# SDRAM_DDR3_4x16.net
KiCad netlist of a schematic drawn in Altium Designer
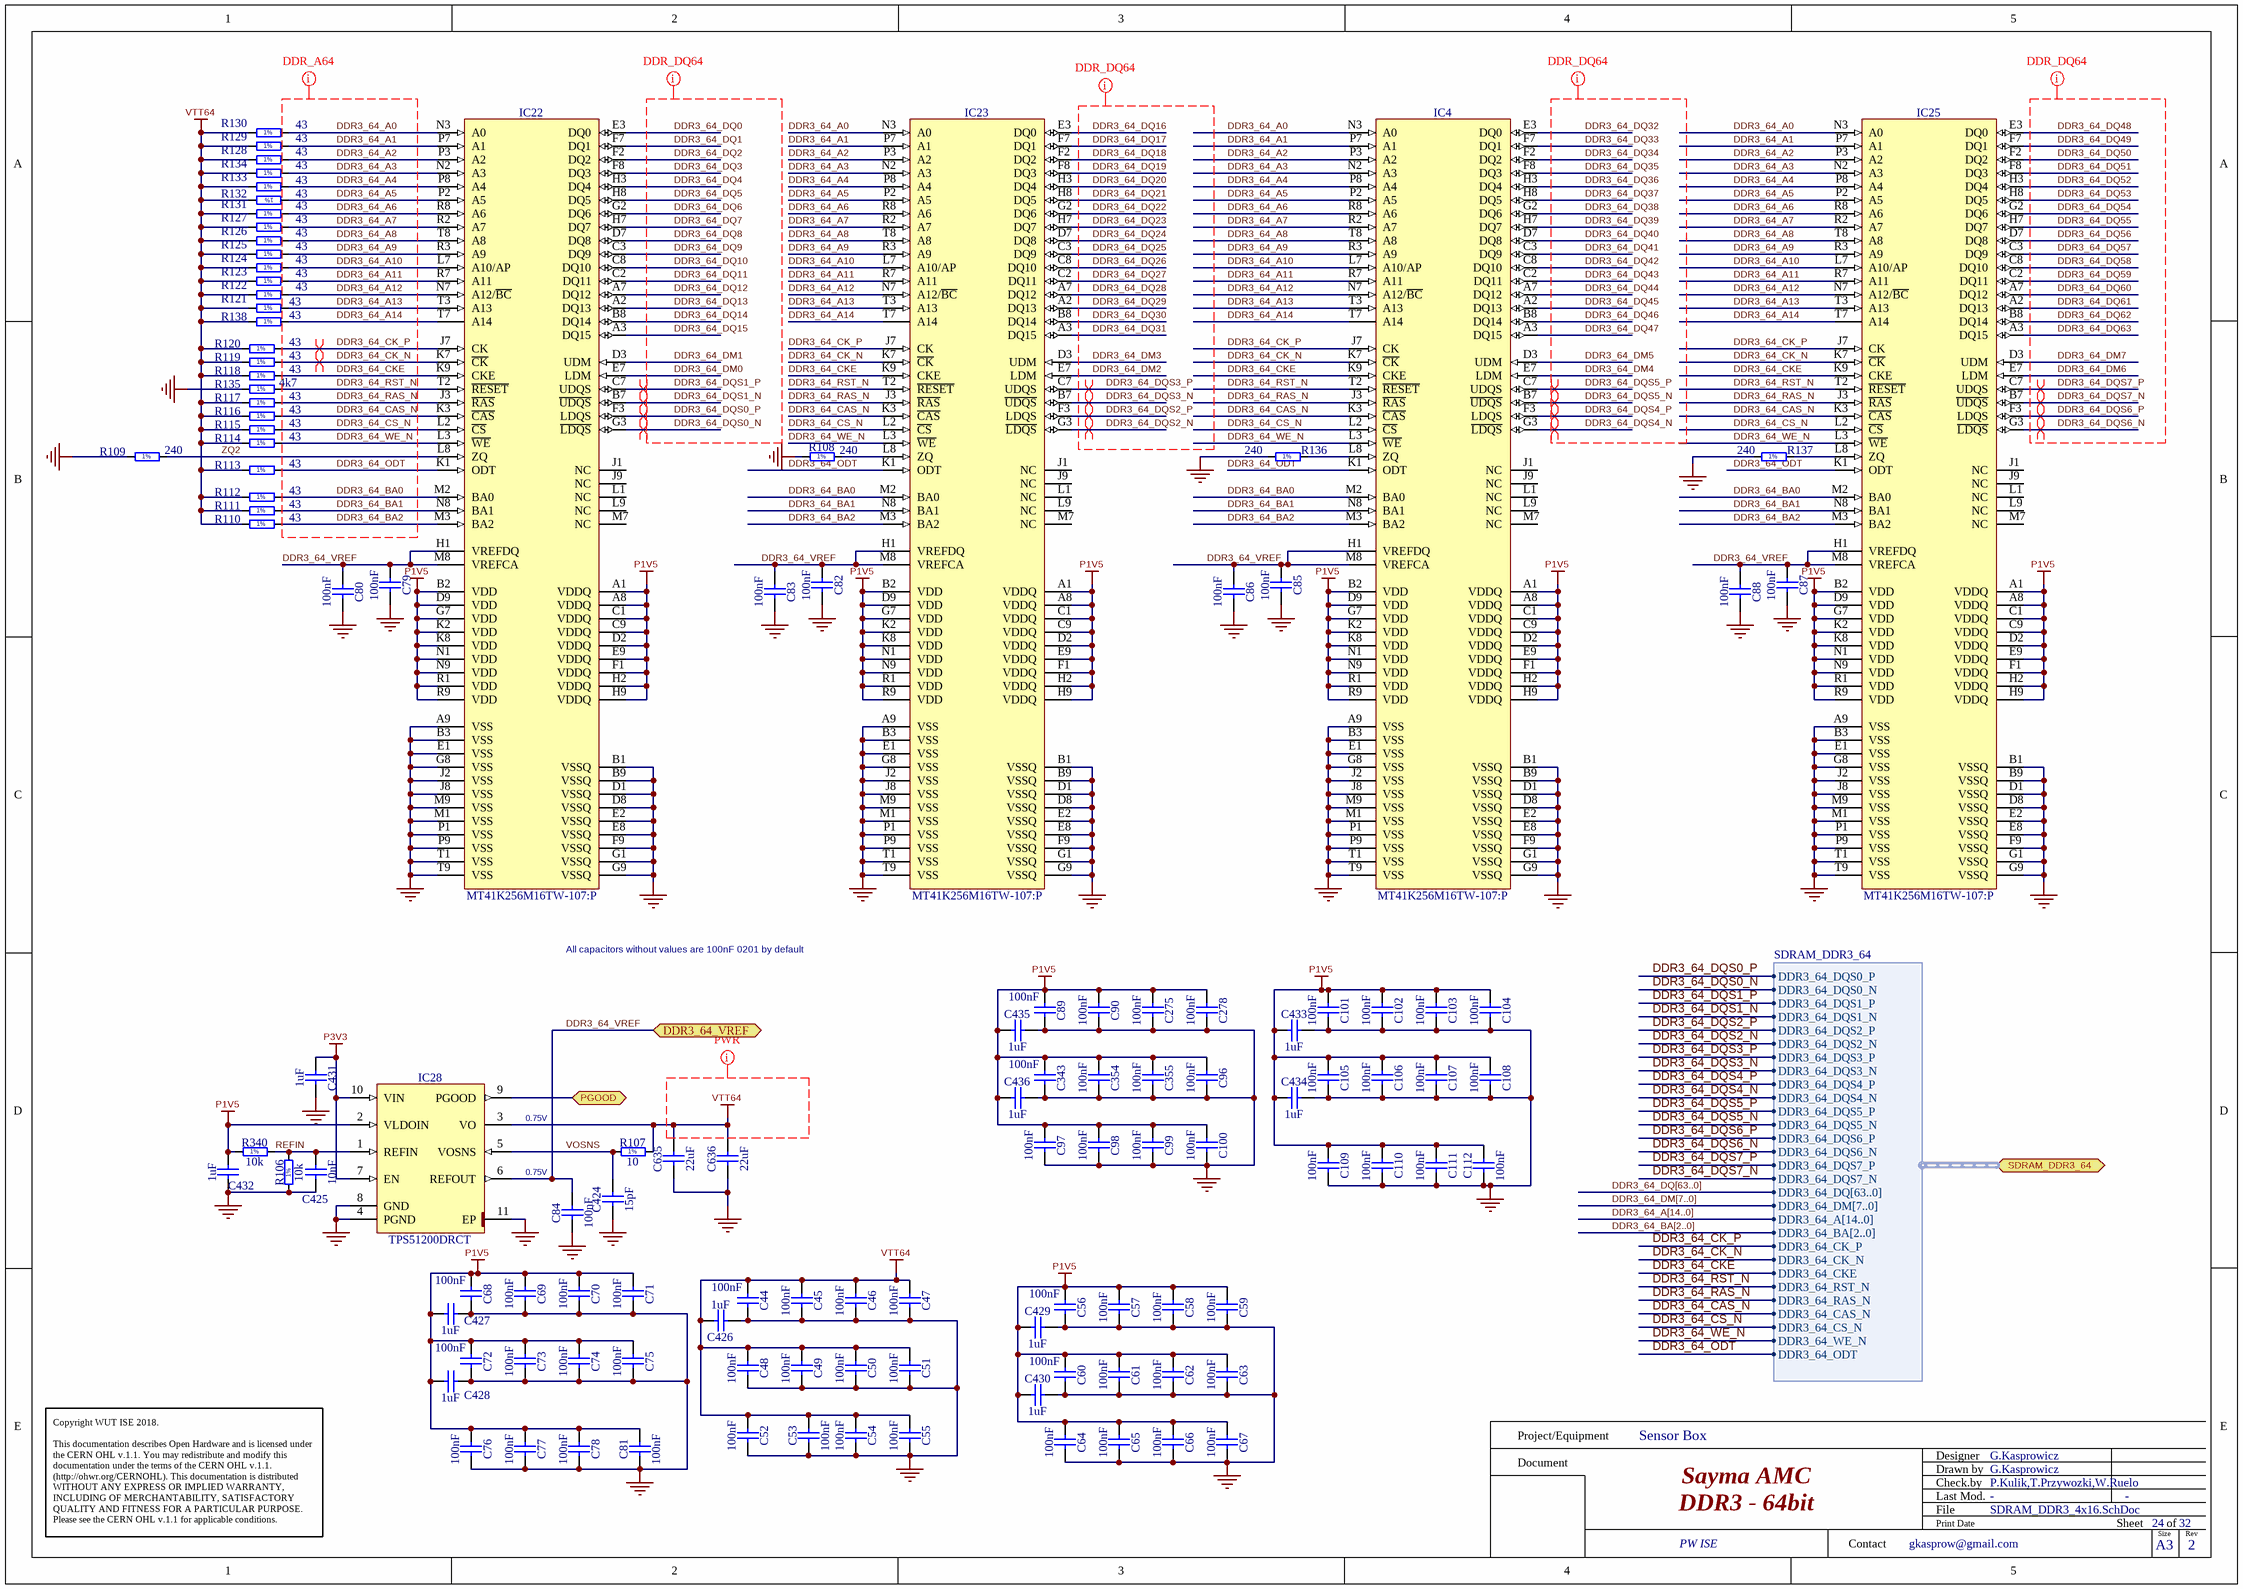
[diagram p0: SDRAM_DDR3_4x16.SchDoc]

(export (version "E")
  (design (tool "Eeschema 10.0.6"))
  (components
    (comp (ref "C44")
      (value "100nF")
      (footprint "CAPC0603X33N")
      (description "Non-polarised capacitor")
      (fields
        (field (name "MANUFACTURER PART NUMBER") "CC0201_100NF_6.3V_10%_X5R")
        (field (name "MANUFACTURER") "GENERIC")
        (field (name "AUTHOR") "CERN DEM JLC")
      )
      (libsource (lib "Capacitors") (part "Capacitor - non polarized"))
    )
    (comp (ref "C45")
      (value "100nF")
      (footprint "CAPC0603X33N")
      (description "Non-polarised capacitor")
      (fields
        (field (name "MANUFACTURER PART NUMBER") "CC0201_100NF_6.3V_10%_X5R")
        (field (name "MANUFACTURER") "GENERIC")
        (field (name "AUTHOR") "CERN DEM JLC")
      )
      (libsource (lib "Capacitors") (part "Capacitor - non polarized"))
    )
    (comp (ref "C46")
      (value "100nF")
      (footprint "CAPC0603X33N")
      (description "Non-polarised capacitor")
      (fields
        (field (name "MANUFACTURER PART NUMBER") "CC0201_100NF_6.3V_10%_X5R")
        (field (name "MANUFACTURER") "GENERIC")
        (field (name "AUTHOR") "CERN DEM JLC")
      )
      (libsource (lib "Capacitors") (part "Capacitor - non polarized"))
    )
    (comp (ref "C47")
      (value "100nF")
      (footprint "CAPC0603X33N")
      (description "Non-polarised capacitor")
      (fields
        (field (name "MANUFACTURER PART NUMBER") "CC0201_100NF_6.3V_10%_X5R")
        (field (name "MANUFACTURER") "GENERIC")
        (field (name "AUTHOR") "CERN DEM JLC")
      )
      (libsource (lib "Capacitors") (part "Capacitor - non polarized"))
    )
    (comp (ref "C48")
      (value "100nF")
      (footprint "CAPC0603X33N")
      (description "Non-polarised capacitor")
      (fields
        (field (name "MANUFACTURER PART NUMBER") "CC0201_100NF_6.3V_10%_X5R")
        (field (name "MANUFACTURER") "GENERIC")
        (field (name "AUTHOR") "CERN DEM JLC")
      )
      (libsource (lib "Capacitors") (part "Capacitor - non polarized"))
    )
    (comp (ref "C49")
      (value "100nF")
      (footprint "CAPC0603X33N")
      (description "Non-polarised capacitor")
      (fields
        (field (name "MANUFACTURER PART NUMBER") "CC0201_100NF_6.3V_10%_X5R")
        (field (name "MANUFACTURER") "GENERIC")
        (field (name "AUTHOR") "CERN DEM JLC")
      )
      (libsource (lib "Capacitors") (part "Capacitor - non polarized"))
    )
    (comp (ref "C50")
      (value "100nF")
      (footprint "CAPC0603X33N")
      (description "Non-polarised capacitor")
      (fields
        (field (name "MANUFACTURER PART NUMBER") "CC0201_100NF_6.3V_10%_X5R")
        (field (name "MANUFACTURER") "GENERIC")
        (field (name "AUTHOR") "CERN DEM JLC")
      )
      (libsource (lib "Capacitors") (part "Capacitor - non polarized"))
    )
    (comp (ref "C51")
      (value "100nF")
      (footprint "CAPC0603X33N")
      (description "Non-polarised capacitor")
      (fields
        (field (name "MANUFACTURER PART NUMBER") "CC0201_100NF_6.3V_10%_X5R")
        (field (name "MANUFACTURER") "GENERIC")
        (field (name "AUTHOR") "CERN DEM JLC")
      )
      (libsource (lib "Capacitors") (part "Capacitor - non polarized"))
    )
    (comp (ref "C52")
      (value "100nF")
      (footprint "CAPC0603X33N")
      (description "Non-polarised capacitor")
      (fields
        (field (name "MANUFACTURER PART NUMBER") "CC0201_100NF_6.3V_10%_X5R")
        (field (name "MANUFACTURER") "GENERIC")
        (field (name "AUTHOR") "CERN DEM JLC")
      )
      (libsource (lib "Capacitors") (part "Capacitor - non polarized"))
    )
    (comp (ref "C53")
      (value "100nF")
      (footprint "CAPC0603X33N")
      (description "Non-polarised capacitor")
      (fields
        (field (name "MANUFACTURER PART NUMBER") "CC0201_100NF_6.3V_10%_X5R")
        (field (name "MANUFACTURER") "GENERIC")
        (field (name "AUTHOR") "CERN DEM JLC")
      )
      (libsource (lib "Capacitors") (part "Capacitor - non polarized"))
    )
    (comp (ref "C54")
      (value "100nF")
      (footprint "CAPC0603X33N")
      (description "Non-polarised capacitor")
      (fields
        (field (name "MANUFACTURER PART NUMBER") "CC0201_100NF_6.3V_10%_X5R")
        (field (name "MANUFACTURER") "GENERIC")
        (field (name "AUTHOR") "CERN DEM JLC")
      )
      (libsource (lib "Capacitors") (part "Capacitor - non polarized"))
    )
    (comp (ref "C55")
      (value "100nF")
      (footprint "CAPC0603X33N")
      (description "Non-polarised capacitor")
      (fields
        (field (name "MANUFACTURER PART NUMBER") "CC0201_100NF_6.3V_10%_X5R")
        (field (name "MANUFACTURER") "GENERIC")
        (field (name "AUTHOR") "CERN DEM JLC")
      )
      (libsource (lib "Capacitors") (part "Capacitor - non polarized"))
    )
    (comp (ref "C56")
      (value "100nF")
      (footprint "CAPC0603X33N")
      (description "Non-polarised capacitor")
      (fields
        (field (name "MANUFACTURER PART NUMBER") "CC0201_100NF_6.3V_10%_X5R")
        (field (name "MANUFACTURER") "GENERIC")
        (field (name "AUTHOR") "CERN DEM JLC")
      )
      (libsource (lib "Capacitors") (part "Capacitor - non polarized"))
    )
    (comp (ref "C57")
      (value "100nF")
      (footprint "CAPC0603X33N")
      (description "Non-polarised capacitor")
      (fields
        (field (name "MANUFACTURER PART NUMBER") "CC0201_100NF_6.3V_10%_X5R")
        (field (name "MANUFACTURER") "GENERIC")
        (field (name "AUTHOR") "CERN DEM JLC")
      )
      (libsource (lib "Capacitors") (part "Capacitor - non polarized"))
    )
    (comp (ref "C58")
      (value "100nF")
      (footprint "CAPC0603X33N")
      (description "Non-polarised capacitor")
      (fields
        (field (name "MANUFACTURER PART NUMBER") "CC0201_100NF_6.3V_10%_X5R")
        (field (name "MANUFACTURER") "GENERIC")
        (field (name "AUTHOR") "CERN DEM JLC")
      )
      (libsource (lib "Capacitors") (part "Capacitor - non polarized"))
    )
    (comp (ref "C59")
      (value "100nF")
      (footprint "CAPC0603X33N")
      (description "Non-polarised capacitor")
      (fields
        (field (name "MANUFACTURER PART NUMBER") "CC0201_100NF_6.3V_10%_X5R")
        (field (name "MANUFACTURER") "GENERIC")
        (field (name "AUTHOR") "CERN DEM JLC")
      )
      (libsource (lib "Capacitors") (part "Capacitor - non polarized"))
    )
    (comp (ref "C60")
      (value "100nF")
      (footprint "CAPC0603X33N")
      (description "Non-polarised capacitor")
      (fields
        (field (name "MANUFACTURER PART NUMBER") "CC0201_100NF_6.3V_10%_X5R")
        (field (name "MANUFACTURER") "GENERIC")
        (field (name "AUTHOR") "CERN DEM JLC")
      )
      (libsource (lib "Capacitors") (part "Capacitor - non polarized"))
    )
    (comp (ref "C61")
      (value "100nF")
      (footprint "CAPC0603X33N")
      (description "Non-polarised capacitor")
      (fields
        (field (name "MANUFACTURER PART NUMBER") "CC0201_100NF_6.3V_10%_X5R")
        (field (name "MANUFACTURER") "GENERIC")
        (field (name "AUTHOR") "CERN DEM JLC")
      )
      (libsource (lib "Capacitors") (part "Capacitor - non polarized"))
    )
    (comp (ref "C62")
      (value "100nF")
      (footprint "CAPC0603X33N")
      (description "Non-polarised capacitor")
      (fields
        (field (name "MANUFACTURER PART NUMBER") "CC0201_100NF_6.3V_10%_X5R")
        (field (name "MANUFACTURER") "GENERIC")
        (field (name "AUTHOR") "CERN DEM JLC")
      )
      (libsource (lib "Capacitors") (part "Capacitor - non polarized"))
    )
    (comp (ref "C63")
      (value "100nF")
      (footprint "CAPC0603X33N")
      (description "Non-polarised capacitor")
      (fields
        (field (name "MANUFACTURER PART NUMBER") "CC0201_100NF_6.3V_10%_X5R")
        (field (name "MANUFACTURER") "GENERIC")
        (field (name "AUTHOR") "CERN DEM JLC")
      )
      (libsource (lib "Capacitors") (part "Capacitor - non polarized"))
    )
    (comp (ref "C64")
      (value "100nF")
      (footprint "CAPC0603X33N")
      (description "Non-polarised capacitor")
      (fields
        (field (name "MANUFACTURER PART NUMBER") "CC0201_100NF_6.3V_10%_X5R")
        (field (name "MANUFACTURER") "GENERIC")
        (field (name "AUTHOR") "CERN DEM JLC")
      )
      (libsource (lib "Capacitors") (part "Capacitor - non polarized"))
    )
    (comp (ref "C65")
      (value "100nF")
      (footprint "CAPC0603X33N")
      (description "Non-polarised capacitor")
      (fields
        (field (name "MANUFACTURER PART NUMBER") "CC0201_100NF_6.3V_10%_X5R")
        (field (name "MANUFACTURER") "GENERIC")
        (field (name "AUTHOR") "CERN DEM JLC")
      )
      (libsource (lib "Capacitors") (part "Capacitor - non polarized"))
    )
    (comp (ref "C66")
      (value "100nF")
      (footprint "CAPC0603X33N")
      (description "Non-polarised capacitor")
      (fields
        (field (name "MANUFACTURER PART NUMBER") "CC0201_100NF_6.3V_10%_X5R")
        (field (name "MANUFACTURER") "GENERIC")
        (field (name "AUTHOR") "CERN DEM JLC")
      )
      (libsource (lib "Capacitors") (part "Capacitor - non polarized"))
    )
    (comp (ref "C67")
      (value "100nF")
      (footprint "CAPC0603X33N")
      (description "Non-polarised capacitor")
      (fields
        (field (name "MANUFACTURER PART NUMBER") "CC0201_100NF_6.3V_10%_X5R")
        (field (name "MANUFACTURER") "GENERIC")
        (field (name "AUTHOR") "CERN DEM JLC")
      )
      (libsource (lib "Capacitors") (part "Capacitor - non polarized"))
    )
    (comp (ref "C68")
      (value "100nF")
      (footprint "CAPC0603X33N")
      (description "Non-polarised capacitor")
      (fields
        (field (name "MANUFACTURER PART NUMBER") "CC0201_100NF_6.3V_10%_X5R")
        (field (name "MANUFACTURER") "GENERIC")
        (field (name "AUTHOR") "CERN DEM JLC")
      )
      (libsource (lib "Capacitors") (part "Capacitor - non polarized"))
    )
    (comp (ref "C69")
      (value "100nF")
      (footprint "CAPC0603X33N")
      (description "Non-polarised capacitor")
      (fields
        (field (name "MANUFACTURER PART NUMBER") "CC0201_100NF_6.3V_10%_X5R")
        (field (name "MANUFACTURER") "GENERIC")
        (field (name "AUTHOR") "CERN DEM JLC")
      )
      (libsource (lib "Capacitors") (part "Capacitor - non polarized"))
    )
    (comp (ref "C70")
      (value "100nF")
      (footprint "CAPC0603X33N")
      (description "Non-polarised capacitor")
      (fields
        (field (name "MANUFACTURER PART NUMBER") "CC0201_100NF_6.3V_10%_X5R")
        (field (name "MANUFACTURER") "GENERIC")
        (field (name "AUTHOR") "CERN DEM JLC")
      )
      (libsource (lib "Capacitors") (part "Capacitor - non polarized"))
    )
    (comp (ref "C71")
      (value "100nF")
      (footprint "CAPC0603X33N")
      (description "Non-polarised capacitor")
      (fields
        (field (name "MANUFACTURER PART NUMBER") "CC0201_100NF_6.3V_10%_X5R")
        (field (name "MANUFACTURER") "GENERIC")
        (field (name "AUTHOR") "CERN DEM JLC")
      )
      (libsource (lib "Capacitors") (part "Capacitor - non polarized"))
    )
    (comp (ref "C72")
      (value "100nF")
      (footprint "CAPC0603X33N")
      (description "Non-polarised capacitor")
      (fields
        (field (name "MANUFACTURER PART NUMBER") "CC0201_100NF_6.3V_10%_X5R")
        (field (name "MANUFACTURER") "GENERIC")
        (field (name "AUTHOR") "CERN DEM JLC")
      )
      (libsource (lib "Capacitors") (part "Capacitor - non polarized"))
    )
    (comp (ref "C73")
      (value "100nF")
      (footprint "CAPC0603X33N")
      (description "Non-polarised capacitor")
      (fields
        (field (name "MANUFACTURER PART NUMBER") "CC0201_100NF_6.3V_10%_X5R")
        (field (name "MANUFACTURER") "GENERIC")
        (field (name "AUTHOR") "CERN DEM JLC")
      )
      (libsource (lib "Capacitors") (part "Capacitor - non polarized"))
    )
    (comp (ref "C74")
      (value "100nF")
      (footprint "CAPC0603X33N")
      (description "Non-polarised capacitor")
      (fields
        (field (name "MANUFACTURER PART NUMBER") "CC0201_100NF_6.3V_10%_X5R")
        (field (name "MANUFACTURER") "GENERIC")
        (field (name "AUTHOR") "CERN DEM JLC")
      )
      (libsource (lib "Capacitors") (part "Capacitor - non polarized"))
    )
    (comp (ref "C75")
      (value "100nF")
      (footprint "CAPC0603X33N")
      (description "Non-polarised capacitor")
      (fields
        (field (name "MANUFACTURER PART NUMBER") "CC0201_100NF_6.3V_10%_X5R")
        (field (name "MANUFACTURER") "GENERIC")
        (field (name "AUTHOR") "CERN DEM JLC")
      )
      (libsource (lib "Capacitors") (part "Capacitor - non polarized"))
    )
    (comp (ref "C76")
      (value "100nF")
      (footprint "CAPC0603X33N")
      (description "Non-polarised capacitor")
      (fields
        (field (name "MANUFACTURER PART NUMBER") "CC0201_100NF_6.3V_10%_X5R")
        (field (name "MANUFACTURER") "GENERIC")
        (field (name "AUTHOR") "CERN DEM JLC")
      )
      (libsource (lib "Capacitors") (part "Capacitor - non polarized"))
    )
    (comp (ref "C77")
      (value "100nF")
      (footprint "CAPC0603X33N")
      (description "Non-polarised capacitor")
      (fields
        (field (name "MANUFACTURER PART NUMBER") "CC0201_100NF_6.3V_10%_X5R")
        (field (name "MANUFACTURER") "GENERIC")
        (field (name "AUTHOR") "CERN DEM JLC")
      )
      (libsource (lib "Capacitors") (part "Capacitor - non polarized"))
    )
    (comp (ref "C78")
      (value "100nF")
      (footprint "CAPC0603X33N")
      (description "Non-polarised capacitor")
      (fields
        (field (name "MANUFACTURER PART NUMBER") "CC0201_100NF_6.3V_10%_X5R")
        (field (name "MANUFACTURER") "GENERIC")
        (field (name "AUTHOR") "CERN DEM JLC")
      )
      (libsource (lib "Capacitors") (part "Capacitor - non polarized"))
    )
    (comp (ref "C79")
      (value "100nF")
      (footprint "CAPC0603X33N")
      (description "Non-polarised capacitor")
      (fields
        (field (name "MANUFACTURER PART NUMBER") "CC0201_100NF_6.3V_10%_X5R")
        (field (name "MANUFACTURER") "GENERIC")
        (field (name "AUTHOR") "CERN DEM JLC")
      )
      (libsource (lib "Capacitors") (part "Capacitor - non polarized"))
    )
    (comp (ref "C80")
      (value "100nF")
      (footprint "CAPC0603X33N")
      (description "Non-polarised capacitor")
      (fields
        (field (name "MANUFACTURER PART NUMBER") "CC0201_100NF_6.3V_10%_X5R")
        (field (name "MANUFACTURER") "GENERIC")
        (field (name "AUTHOR") "CERN DEM JLC")
      )
      (libsource (lib "Capacitors") (part "Capacitor - non polarized"))
    )
    (comp (ref "C81")
      (value "100nF")
      (footprint "CAPC0603X33N")
      (description "Non-polarised capacitor")
      (fields
        (field (name "MANUFACTURER PART NUMBER") "CC0201_100NF_6.3V_10%_X5R")
        (field (name "MANUFACTURER") "GENERIC")
        (field (name "AUTHOR") "CERN DEM JLC")
      )
      (libsource (lib "Capacitors") (part "Capacitor - non polarized"))
    )
    (comp (ref "C82")
      (value "100nF")
      (footprint "CAPC0603X33N")
      (description "Non-polarised capacitor")
      (fields
        (field (name "MANUFACTURER PART NUMBER") "CC0201_100NF_6.3V_10%_X5R")
        (field (name "MANUFACTURER") "GENERIC")
        (field (name "AUTHOR") "CERN DEM JLC")
      )
      (libsource (lib "Capacitors") (part "Capacitor - non polarized"))
    )
    (comp (ref "C83")
      (value "100nF")
      (footprint "CAPC0603X33N")
      (description "Non-polarised capacitor")
      (fields
        (field (name "MANUFACTURER PART NUMBER") "CC0201_100NF_6.3V_10%_X5R")
        (field (name "MANUFACTURER") "GENERIC")
        (field (name "AUTHOR") "CERN DEM JLC")
      )
      (libsource (lib "Capacitors") (part "Capacitor - non polarized"))
    )
    (comp (ref "C84")
      (value "100nF")
      (footprint "CAPC0603X33N")
      (description "Non-polarised capacitor")
      (fields
        (field (name "MANUFACTURER PART NUMBER") "CC0201_100NF_6.3V_10%_X5R")
        (field (name "MANUFACTURER") "GENERIC")
        (field (name "AUTHOR") "CERN DEM JLC")
      )
      (libsource (lib "Capacitors") (part "Capacitor - non polarized"))
    )
    (comp (ref "C85")
      (value "100nF")
      (footprint "CAPC0603X33N")
      (description "Non-polarised capacitor")
      (fields
        (field (name "MANUFACTURER PART NUMBER") "CC0201_100NF_6.3V_10%_X5R")
        (field (name "MANUFACTURER") "GENERIC")
        (field (name "AUTHOR") "CERN DEM JLC")
      )
      (libsource (lib "Capacitors") (part "Capacitor - non polarized"))
    )
    (comp (ref "C86")
      (value "100nF")
      (footprint "CAPC0603X33N")
      (description "Non-polarised capacitor")
      (fields
        (field (name "MANUFACTURER PART NUMBER") "CC0201_100NF_6.3V_10%_X5R")
        (field (name "MANUFACTURER") "GENERIC")
        (field (name "AUTHOR") "CERN DEM JLC")
      )
      (libsource (lib "Capacitors") (part "Capacitor - non polarized"))
    )
    (comp (ref "C87")
      (value "100nF")
      (footprint "CAPC0603X33N")
      (description "Non-polarised capacitor")
      (fields
        (field (name "MANUFACTURER PART NUMBER") "CC0201_100NF_6.3V_10%_X5R")
        (field (name "MANUFACTURER") "GENERIC")
        (field (name "AUTHOR") "CERN DEM JLC")
      )
      (libsource (lib "Capacitors") (part "Capacitor - non polarized"))
    )
    (comp (ref "C88")
      (value "100nF")
      (footprint "CAPC0603X33N")
      (description "Non-polarised capacitor")
      (fields
        (field (name "MANUFACTURER PART NUMBER") "CC0201_100NF_6.3V_10%_X5R")
        (field (name "MANUFACTURER") "GENERIC")
        (field (name "AUTHOR") "CERN DEM JLC")
      )
      (libsource (lib "Capacitors") (part "Capacitor - non polarized"))
    )
    (comp (ref "C89")
      (value "100nF")
      (footprint "CAPC0603X33N")
      (description "Non-polarised capacitor")
      (fields
        (field (name "MANUFACTURER PART NUMBER") "CC0201_100NF_6.3V_10%_X5R")
        (field (name "MANUFACTURER") "GENERIC")
        (field (name "AUTHOR") "CERN DEM JLC")
      )
      (libsource (lib "Capacitors") (part "Capacitor - non polarized"))
    )
    (comp (ref "C90")
      (value "100nF")
      (footprint "CAPC0603X33N")
      (description "Non-polarised capacitor")
      (fields
        (field (name "MANUFACTURER PART NUMBER") "CC0201_100NF_6.3V_10%_X5R")
        (field (name "MANUFACTURER") "GENERIC")
        (field (name "AUTHOR") "CERN DEM JLC")
      )
      (libsource (lib "Capacitors") (part "Capacitor - non polarized"))
    )
    (comp (ref "C96")
      (value "100nF")
      (footprint "CAPC0603X33N")
      (description "Non-polarised capacitor")
      (fields
        (field (name "MANUFACTURER PART NUMBER") "CC0201_100NF_6.3V_10%_X5R")
        (field (name "MANUFACTURER") "GENERIC")
        (field (name "AUTHOR") "CERN DEM JLC")
      )
      (libsource (lib "Capacitors") (part "Capacitor - non polarized"))
    )
    (comp (ref "C97")
      (value "100nF")
      (footprint "CAPC0603X33N")
      (description "Non-polarised capacitor")
      (fields
        (field (name "MANUFACTURER PART NUMBER") "CC0201_100NF_6.3V_10%_X5R")
        (field (name "MANUFACTURER") "GENERIC")
        (field (name "AUTHOR") "CERN DEM JLC")
      )
      (libsource (lib "Capacitors") (part "Capacitor - non polarized"))
    )
    (comp (ref "C98")
      (value "100nF")
      (footprint "CAPC0603X33N")
      (description "Non-polarised capacitor")
      (fields
        (field (name "MANUFACTURER PART NUMBER") "CC0201_100NF_6.3V_10%_X5R")
        (field (name "MANUFACTURER") "GENERIC")
        (field (name "AUTHOR") "CERN DEM JLC")
      )
      (libsource (lib "Capacitors") (part "Capacitor - non polarized"))
    )
    (comp (ref "C99")
      (value "100nF")
      (footprint "CAPC0603X33N")
      (description "Non-polarised capacitor")
      (fields
        (field (name "MANUFACTURER PART NUMBER") "CC0201_100NF_6.3V_10%_X5R")
        (field (name "MANUFACTURER") "GENERIC")
        (field (name "AUTHOR") "CERN DEM JLC")
      )
      (libsource (lib "Capacitors") (part "Capacitor - non polarized"))
    )
    (comp (ref "C100")
      (value "100nF")
      (footprint "CAPC0603X33N")
      (description "Non-polarised capacitor")
      (fields
        (field (name "MANUFACTURER PART NUMBER") "CC0201_100NF_6.3V_10%_X5R")
        (field (name "MANUFACTURER") "GENERIC")
        (field (name "AUTHOR") "CERN DEM JLC")
      )
      (libsource (lib "Capacitors") (part "Capacitor - non polarized"))
    )
    (comp (ref "C101")
      (value "100nF")
      (footprint "CAPC0603X33N")
      (description "Non-polarised capacitor")
      (fields
        (field (name "MANUFACTURER PART NUMBER") "CC0201_100NF_6.3V_10%_X5R")
        (field (name "MANUFACTURER") "GENERIC")
        (field (name "AUTHOR") "CERN DEM JLC")
      )
      (libsource (lib "Capacitors") (part "Capacitor - non polarized"))
    )
    (comp (ref "C102")
      (value "100nF")
      (footprint "CAPC0603X33N")
      (description "Non-polarised capacitor")
      (fields
        (field (name "MANUFACTURER PART NUMBER") "CC0201_100NF_6.3V_10%_X5R")
        (field (name "MANUFACTURER") "GENERIC")
        (field (name "AUTHOR") "CERN DEM JLC")
      )
      (libsource (lib "Capacitors") (part "Capacitor - non polarized"))
    )
    (comp (ref "C103")
      (value "100nF")
      (footprint "CAPC0603X33N")
      (description "Non-polarised capacitor")
      (fields
        (field (name "MANUFACTURER PART NUMBER") "CC0201_100NF_6.3V_10%_X5R")
        (field (name "MANUFACTURER") "GENERIC")
        (field (name "AUTHOR") "CERN DEM JLC")
      )
      (libsource (lib "Capacitors") (part "Capacitor - non polarized"))
    )
    (comp (ref "C104")
      (value "100nF")
      (footprint "CAPC0603X33N")
      (description "Non-polarised capacitor")
      (fields
        (field (name "MANUFACTURER PART NUMBER") "CC0201_100NF_6.3V_10%_X5R")
        (field (name "MANUFACTURER") "GENERIC")
        (field (name "AUTHOR") "CERN DEM JLC")
      )
      (libsource (lib "Capacitors") (part "Capacitor - non polarized"))
    )
    (comp (ref "C105")
      (value "100nF")
      (footprint "CAPC0603X33N")
      (description "Non-polarised capacitor")
      (fields
        (field (name "MANUFACTURER PART NUMBER") "CC0201_100NF_6.3V_10%_X5R")
        (field (name "MANUFACTURER") "GENERIC")
        (field (name "AUTHOR") "CERN DEM JLC")
      )
      (libsource (lib "Capacitors") (part "Capacitor - non polarized"))
    )
    (comp (ref "C106")
      (value "100nF")
      (footprint "CAPC0603X33N")
      (description "Non-polarised capacitor")
      (fields
        (field (name "MANUFACTURER PART NUMBER") "CC0201_100NF_6.3V_10%_X5R")
        (field (name "MANUFACTURER") "GENERIC")
        (field (name "AUTHOR") "CERN DEM JLC")
      )
      (libsource (lib "Capacitors") (part "Capacitor - non polarized"))
    )
    (comp (ref "C107")
      (value "100nF")
      (footprint "CAPC0603X33N")
      (description "Non-polarised capacitor")
      (fields
        (field (name "MANUFACTURER PART NUMBER") "CC0201_100NF_6.3V_10%_X5R")
        (field (name "MANUFACTURER") "GENERIC")
        (field (name "AUTHOR") "CERN DEM JLC")
      )
      (libsource (lib "Capacitors") (part "Capacitor - non polarized"))
    )
    (comp (ref "C108")
      (value "100nF")
      (footprint "CAPC0603X33N")
      (description "Non-polarised capacitor")
      (fields
        (field (name "MANUFACTURER PART NUMBER") "CC0201_100NF_6.3V_10%_X5R")
        (field (name "MANUFACTURER") "GENERIC")
        (field (name "AUTHOR") "CERN DEM JLC")
      )
      (libsource (lib "Capacitors") (part "Capacitor - non polarized"))
    )
    (comp (ref "C109")
      (value "100nF")
      (footprint "CAPC0603X33N")
      (description "Non-polarised capacitor")
      (fields
        (field (name "MANUFACTURER PART NUMBER") "CC0201_100NF_6.3V_10%_X5R")
        (field (name "MANUFACTURER") "GENERIC")
        (field (name "AUTHOR") "CERN DEM JLC")
      )
      (libsource (lib "Capacitors") (part "Capacitor - non polarized"))
    )
    (comp (ref "C110")
      (value "100nF")
      (footprint "CAPC0603X33N")
      (description "Non-polarised capacitor")
      (fields
        (field (name "MANUFACTURER PART NUMBER") "CC0201_100NF_6.3V_10%_X5R")
        (field (name "MANUFACTURER") "GENERIC")
        (field (name "AUTHOR") "CERN DEM JLC")
      )
      (libsource (lib "Capacitors") (part "Capacitor - non polarized"))
    )
    (comp (ref "C111")
      (value "100nF")
      (footprint "CAPC0603X33N")
      (description "Non-polarised capacitor")
      (fields
        (field (name "MANUFACTURER PART NUMBER") "CC0201_100NF_6.3V_10%_X5R")
        (field (name "MANUFACTURER") "GENERIC")
        (field (name "AUTHOR") "CERN DEM JLC")
      )
      (libsource (lib "Capacitors") (part "Capacitor - non polarized"))
    )
    (comp (ref "C112")
      (value "100nF")
      (footprint "CAPC0603X33N")
      (description "Non-polarised capacitor")
      (fields
        (field (name "MANUFACTURER PART NUMBER") "CC0201_100NF_6.3V_10%_X5R")
        (field (name "MANUFACTURER") "GENERIC")
        (field (name "AUTHOR") "CERN DEM JLC")
      )
      (libsource (lib "Capacitors") (part "Capacitor - non polarized"))
    )
    (comp (ref "C275")
      (value "100nF")
      (footprint "CAPC0603X33N")
      (description "Non-polarised capacitor")
      (fields
        (field (name "MANUFACTURER PART NUMBER") "CC0201_100NF_6.3V_10%_X5R")
        (field (name "MANUFACTURER") "GENERIC")
        (field (name "AUTHOR") "CERN DEM JLC")
      )
      (libsource (lib "Capacitors") (part "Capacitor - non polarized"))
    )
    (comp (ref "C278")
      (value "100nF")
      (footprint "CAPC0603X33N")
      (description "Non-polarised capacitor")
      (fields
        (field (name "MANUFACTURER PART NUMBER") "CC0201_100NF_6.3V_10%_X5R")
        (field (name "MANUFACTURER") "GENERIC")
        (field (name "AUTHOR") "CERN DEM JLC")
      )
      (libsource (lib "Capacitors") (part "Capacitor - non polarized"))
    )
    (comp (ref "C343")
      (value "100nF")
      (footprint "CAPC0603X33N")
      (description "Non-polarised capacitor")
      (fields
        (field (name "MANUFACTURER PART NUMBER") "CC0201_100NF_6.3V_10%_X5R")
        (field (name "MANUFACTURER") "GENERIC")
        (field (name "AUTHOR") "CERN DEM JLC")
      )
      (libsource (lib "Capacitors") (part "Capacitor - non polarized"))
    )
    (comp (ref "C354")
      (value "100nF")
      (footprint "CAPC0603X33N")
      (description "Non-polarised capacitor")
      (fields
        (field (name "MANUFACTURER PART NUMBER") "CC0201_100NF_6.3V_10%_X5R")
        (field (name "MANUFACTURER") "GENERIC")
        (field (name "AUTHOR") "CERN DEM JLC")
      )
      (libsource (lib "Capacitors") (part "Capacitor - non polarized"))
    )
    (comp (ref "C355")
      (value "100nF")
      (footprint "CAPC0603X33N")
      (description "Non-polarised capacitor")
      (fields
        (field (name "MANUFACTURER PART NUMBER") "CC0201_100NF_6.3V_10%_X5R")
        (field (name "MANUFACTURER") "GENERIC")
        (field (name "AUTHOR") "CERN DEM JLC")
      )
      (libsource (lib "Capacitors") (part "Capacitor - non polarized"))
    )
    (comp (ref "C424")
      (value "15pF")
      (footprint "CAPC1005X55N")
      (description "Non-polarised capacitor")
      (fields
        (field (name "MANUFACTURER PART NUMBER") "CC0402_15PF_50V_5%_C0G")
        (field (name "MANUFACTURER") "GENERIC")
        (field (name "AUTHOR") "CERN DEM JLC")
      )
      (libsource (lib "Capacitors") (part "Capacitor - non polarized"))
    )
    (comp (ref "C425")
      (value "10nF")
      (footprint "CAPC1005X55N")
      (description "Non-polarised capacitor")
      (fields
        (field (name "MANUFACTURER PART NUMBER") "CC0402_10NF_25V_10%_X7R")
        (field (name "MANUFACTURER") "GENERIC")
        (field (name "AUTHOR") "CERN DEM JLC")
      )
      (libsource (lib "Capacitors") (part "Capacitor - non polarized"))
    )
    (comp (ref "C426")
      (value "1uF")
      (footprint "CAPC1005X55N")
      (description "Non-polarised capacitor")
      (fields
        (field (name "MANUFACTURER PART NUMBER") "CC0402_1UF_16V_10%_X5R")
        (field (name "MANUFACTURER") "GENERIC")
        (field (name "AUTHOR") "CERN DEM JLC")
      )
      (libsource (lib "Capacitors") (part "Capacitor - non polarized"))
    )
    (comp (ref "C427")
      (value "1uF")
      (footprint "CAPC1005X55N")
      (description "Non-polarised capacitor")
      (fields
        (field (name "MANUFACTURER PART NUMBER") "CC0402_1UF_16V_10%_X5R")
        (field (name "MANUFACTURER") "GENERIC")
        (field (name "AUTHOR") "CERN DEM JLC")
      )
      (libsource (lib "Capacitors") (part "Capacitor - non polarized"))
    )
    (comp (ref "C428")
      (value "1uF")
      (footprint "CAPC1005X55N")
      (description "Non-polarised capacitor")
      (fields
        (field (name "MANUFACTURER PART NUMBER") "CC0402_1UF_16V_10%_X5R")
        (field (name "MANUFACTURER") "GENERIC")
        (field (name "AUTHOR") "CERN DEM JLC")
      )
      (libsource (lib "Capacitors") (part "Capacitor - non polarized"))
    )
    (comp (ref "C429")
      (value "1uF")
      (footprint "CAPC1005X55N")
      (description "Non-polarised capacitor")
      (fields
        (field (name "MANUFACTURER PART NUMBER") "CC0402_1UF_16V_10%_X5R")
        (field (name "MANUFACTURER") "GENERIC")
        (field (name "AUTHOR") "CERN DEM JLC")
      )
      (libsource (lib "Capacitors") (part "Capacitor - non polarized"))
    )
    (comp (ref "C430")
      (value "1uF")
      (footprint "CAPC1005X55N")
      (description "Non-polarised capacitor")
      (fields
        (field (name "MANUFACTURER PART NUMBER") "CC0402_1UF_16V_10%_X5R")
        (field (name "MANUFACTURER") "GENERIC")
        (field (name "AUTHOR") "CERN DEM JLC")
      )
      (libsource (lib "Capacitors") (part "Capacitor - non polarized"))
    )
    (comp (ref "C431")
      (value "1uF")
      (footprint "CAPC1005X55N")
      (description "Non-polarised capacitor")
      (fields
        (field (name "MANUFACTURER PART NUMBER") "CC0402_1UF_16V_10%_X5R")
        (field (name "MANUFACTURER") "GENERIC")
        (field (name "AUTHOR") "CERN DEM JLC")
      )
      (libsource (lib "Capacitors") (part "Capacitor - non polarized"))
    )
    (comp (ref "C432")
      (value "1uF")
      (footprint "CAPC1005X55N")
      (description "Non-polarised capacitor")
      (fields
        (field (name "MANUFACTURER PART NUMBER") "CC0402_1UF_16V_10%_X5R")
        (field (name "MANUFACTURER") "GENERIC")
        (field (name "AUTHOR") "CERN DEM JLC")
      )
      (libsource (lib "Capacitors") (part "Capacitor - non polarized"))
    )
    (comp (ref "C433")
      (value "1uF")
      (footprint "CAPC1005X55N")
      (description "Non-polarised capacitor")
      (fields
        (field (name "MANUFACTURER PART NUMBER") "CC0402_1UF_16V_10%_X5R")
        (field (name "MANUFACTURER") "GENERIC")
        (field (name "AUTHOR") "CERN DEM JLC")
      )
      (libsource (lib "Capacitors") (part "Capacitor - non polarized"))
    )
    (comp (ref "C434")
      (value "1uF")
      (footprint "CAPC1005X55N")
      (description "Non-polarised capacitor")
      (fields
        (field (name "MANUFACTURER PART NUMBER") "CC0402_1UF_16V_10%_X5R")
        (field (name "MANUFACTURER") "GENERIC")
        (field (name "AUTHOR") "CERN DEM JLC")
      )
      (libsource (lib "Capacitors") (part "Capacitor - non polarized"))
    )
    (comp (ref "C435")
      (value "1uF")
      (footprint "CAPC1005X55N")
      (description "Non-polarised capacitor")
      (fields
        (field (name "MANUFACTURER PART NUMBER") "CC0402_1UF_16V_10%_X5R")
        (field (name "MANUFACTURER") "GENERIC")
        (field (name "AUTHOR") "CERN DEM JLC")
      )
      (libsource (lib "Capacitors") (part "Capacitor - non polarized"))
    )
    (comp (ref "C436")
      (value "1uF")
      (footprint "CAPC1005X55N")
      (description "Non-polarised capacitor")
      (fields
        (field (name "MANUFACTURER PART NUMBER") "CC0402_1UF_16V_10%_X5R")
        (field (name "MANUFACTURER") "GENERIC")
        (field (name "AUTHOR") "CERN DEM JLC")
      )
      (libsource (lib "Capacitors") (part "Capacitor - non polarized"))
    )
    (comp (ref "C635")
      (value "22uF")
      (footprint "CAPC2012X135N")
      (description "Non-polarised capacitor")
      (fields
        (field (name "MANUFACTURER PART NUMBER") "CC0805_22UF_10V_+80%-20%_Y5V")
        (field (name "MANUFACTURER") "GENERIC")
        (field (name "AUTHOR") "CERN DEM JLC")
      )
      (libsource (lib "Capacitors") (part "Capacitor - non polarized"))
    )
    (comp (ref "C636")
      (value "22uF")
      (footprint "CAPC2012X135N")
      (description "Non-polarised capacitor")
      (fields
        (field (name "MANUFACTURER PART NUMBER") "CC0805_22UF_10V_+80%-20%_Y5V")
        (field (name "MANUFACTURER") "GENERIC")
        (field (name "AUTHOR") "CERN DEM JLC")
      )
      (libsource (lib "Capacitors") (part "Capacitor - non polarized"))
    )
    (comp (ref "IC4")
      (value "MT41K256M16TW-107:P")
      (footprint "BGA96C80P9X16_800X1400X120")
      (description "32 Meg x 16 x 8 Banks DDR3L SDRAM")
      (fields (field (name "MANUFACTURER") "MICRON TECHNOLOGY") (field (name "AUTHOR") "CERN DEM MR"))
      (libsource (lib "ICs And Semiconductors") (part "MT41K256M16TW-107{colon}P"))
    )
    (comp (ref "IC22")
      (value "MT41K256M16TW-107:P")
      (footprint "BGA96C80P9X16_800X1400X120")
      (description "32 Meg x 16 x 8 Banks DDR3L SDRAM")
      (fields (field (name "MANUFACTURER") "MICRON TECHNOLOGY") (field (name "AUTHOR") "CERN DEM MR"))
      (libsource (lib "ICs And Semiconductors") (part "MT41K256M16TW-107{colon}P"))
    )
    (comp (ref "IC23")
      (value "MT41K256M16TW-107:P")
      (footprint "BGA96C80P9X16_800X1400X120")
      (description "32 Meg x 16 x 8 Banks DDR3L SDRAM")
      (fields (field (name "MANUFACTURER") "MICRON TECHNOLOGY") (field (name "AUTHOR") "CERN DEM MR"))
      (libsource (lib "ICs And Semiconductors") (part "MT41K256M16TW-107{colon}P"))
    )
    (comp (ref "IC25")
      (value "MT41K256M16TW-107:P")
      (footprint "BGA96C80P9X16_800X1400X120")
      (description "32 Meg x 16 x 8 Banks DDR3L SDRAM")
      (fields (field (name "MANUFACTURER") "MICRON TECHNOLOGY") (field (name "AUTHOR") "CERN DEM MR"))
      (libsource (lib "ICs And Semiconductors") (part "MT41K256M16TW-107{colon}P"))
    )
    (comp (ref "IC28")
      (value "TPS51200DRCT")
      (footprint "TEXAS_DRC (S-PVSON-N10)")
      (description "Sink/Source DDR Termination Regulator")
      (fields (field (name "MANUFACTURER") "TEXAS INSTRUMENTS") (field (name "AUTHOR") "CERN DEM JLC"))
      (libsource (lib "ICs And Semiconductors") (part "TPS51200DRC"))
    )
    (comp (ref "R106")
      (value "10k")
      (footprint "RESC1005X40N")
      (description "Resistor - 1%")
      (fields
        (field (name "MANUFACTURER PART NUMBER") "R0402_10K_1%_0.0625W_100PPM")
        (field (name "MANUFACTURER") "GENERIC")
        (field (name "AUTHOR") "CERN DEM JLC")
      )
      (libsource (lib "Resistors") (part "Resistor - 1%"))
    )
    (comp (ref "R107")
      (value "10")
      (footprint "RESC1005X40N")
      (description "Resistor - 1%")
      (fields
        (field (name "MANUFACTURER PART NUMBER") "R0402_10R_1%_0.0625W_200PPM")
        (field (name "MANUFACTURER") "GENERIC")
        (field (name "AUTHOR") "CERN DEM JLC")
      )
      (libsource (lib "Resistors") (part "Resistor - 1%"))
    )
    (comp (ref "R108")
      (value "240")
      (footprint "RESC1005X40N")
      (description "Resistor - 1%")
      (fields
        (field (name "MANUFACTURER PART NUMBER") "R0402_240R_1%_0.0625W_100PPM")
        (field (name "MANUFACTURER") "GENERIC")
        (field (name "AUTHOR") "CERN DEM JLC")
      )
      (libsource (lib "Resistors") (part "Resistor - 1%"))
    )
    (comp (ref "R109")
      (value "240")
      (footprint "RESC1005X40N")
      (description "Resistor - 1%")
      (fields
        (field (name "MANUFACTURER PART NUMBER") "R0402_240R_1%_0.0625W_100PPM")
        (field (name "MANUFACTURER") "GENERIC")
        (field (name "AUTHOR") "CERN DEM JLC")
      )
      (libsource (lib "Resistors") (part "Resistor - 1%"))
    )
    (comp (ref "R110")
      (value "43")
      (footprint "RESC1005X40N")
      (description "Resistor - 1%")
      (fields
        (field (name "MANUFACTURER PART NUMBER") "R0402_43R_1%_0.0625W_100PPM")
        (field (name "MANUFACTURER") "GENERIC")
        (field (name "AUTHOR") "CERN DEM JLC")
      )
      (libsource (lib "Resistors") (part "Resistor - 1%"))
    )
    (comp (ref "R111")
      (value "43")
      (footprint "RESC1005X40N")
      (description "Resistor - 1%")
      (fields
        (field (name "MANUFACTURER PART NUMBER") "R0402_43R_1%_0.0625W_100PPM")
        (field (name "MANUFACTURER") "GENERIC")
        (field (name "AUTHOR") "CERN DEM JLC")
      )
      (libsource (lib "Resistors") (part "Resistor - 1%"))
    )
    (comp (ref "R112")
      (value "43")
      (footprint "RESC1005X40N")
      (description "Resistor - 1%")
      (fields
        (field (name "MANUFACTURER PART NUMBER") "R0402_43R_1%_0.0625W_100PPM")
        (field (name "MANUFACTURER") "GENERIC")
        (field (name "AUTHOR") "CERN DEM JLC")
      )
      (libsource (lib "Resistors") (part "Resistor - 1%"))
    )
    (comp (ref "R113")
      (value "43")
      (footprint "RESC1005X40N")
      (description "Resistor - 1%")
      (fields
        (field (name "MANUFACTURER PART NUMBER") "R0402_43R_1%_0.0625W_100PPM")
        (field (name "MANUFACTURER") "GENERIC")
        (field (name "AUTHOR") "CERN DEM JLC")
      )
      (libsource (lib "Resistors") (part "Resistor - 1%"))
    )
    (comp (ref "R114")
      (value "43")
      (footprint "RESC1005X40N")
      (description "Resistor - 1%")
      (fields
        (field (name "MANUFACTURER PART NUMBER") "R0402_43R_1%_0.0625W_100PPM")
        (field (name "MANUFACTURER") "GENERIC")
        (field (name "AUTHOR") "CERN DEM JLC")
      )
      (libsource (lib "Resistors") (part "Resistor - 1%"))
    )
    (comp (ref "R115")
      (value "43")
      (footprint "RESC1005X40N")
      (description "Resistor - 1%")
      (fields
        (field (name "MANUFACTURER PART NUMBER") "R0402_43R_1%_0.0625W_100PPM")
        (field (name "MANUFACTURER") "GENERIC")
        (field (name "AUTHOR") "CERN DEM JLC")
      )
      (libsource (lib "Resistors") (part "Resistor - 1%"))
    )
    (comp (ref "R116")
      (value "43")
      (footprint "RESC1005X40N")
      (description "Resistor - 1%")
      (fields
        (field (name "MANUFACTURER PART NUMBER") "R0402_43R_1%_0.0625W_100PPM")
        (field (name "MANUFACTURER") "GENERIC")
        (field (name "AUTHOR") "CERN DEM JLC")
      )
      (libsource (lib "Resistors") (part "Resistor - 1%"))
    )
    (comp (ref "R117")
      (value "43")
      (footprint "RESC1005X40N")
      (description "Resistor - 1%")
      (fields
        (field (name "MANUFACTURER PART NUMBER") "R0402_43R_1%_0.0625W_100PPM")
        (field (name "MANUFACTURER") "GENERIC")
        (field (name "AUTHOR") "CERN DEM JLC")
      )
      (libsource (lib "Resistors") (part "Resistor - 1%"))
    )
    (comp (ref "R118")
      (value "43")
      (footprint "RESC1005X40N")
      (description "Resistor - 1%")
      (fields
        (field (name "MANUFACTURER PART NUMBER") "R0402_43R_1%_0.0625W_100PPM")
        (field (name "MANUFACTURER") "GENERIC")
        (field (name "AUTHOR") "CERN DEM JLC")
      )
      (libsource (lib "Resistors") (part "Resistor - 1%"))
    )
    (comp (ref "R119")
      (value "43")
      (footprint "RESC1005X40N")
      (description "Resistor - 1%")
      (fields
        (field (name "MANUFACTURER PART NUMBER") "R0402_43R_1%_0.0625W_100PPM")
        (field (name "MANUFACTURER") "GENERIC")
        (field (name "AUTHOR") "CERN DEM JLC")
      )
      (libsource (lib "Resistors") (part "Resistor - 1%"))
    )
    (comp (ref "R120")
      (value "43")
      (footprint "RESC1005X40N")
      (description "Resistor - 1%")
      (fields
        (field (name "MANUFACTURER PART NUMBER") "R0402_43R_1%_0.0625W_100PPM")
        (field (name "MANUFACTURER") "GENERIC")
        (field (name "AUTHOR") "CERN DEM JLC")
      )
      (libsource (lib "Resistors") (part "Resistor - 1%"))
    )
    (comp (ref "R121")
      (value "43")
      (footprint "RESC1005X40N")
      (description "Resistor - 1%")
      (fields
        (field (name "MANUFACTURER PART NUMBER") "R0402_43R_1%_0.0625W_100PPM")
        (field (name "MANUFACTURER") "GENERIC")
        (field (name "AUTHOR") "CERN DEM JLC")
      )
      (libsource (lib "Resistors") (part "Resistor - 1%"))
    )
    (comp (ref "R122")
      (value "43")
      (footprint "RESC1005X40N")
      (description "Resistor - 1%")
      (fields
        (field (name "MANUFACTURER PART NUMBER") "R0402_43R_1%_0.0625W_100PPM")
        (field (name "MANUFACTURER") "GENERIC")
        (field (name "AUTHOR") "CERN DEM JLC")
      )
      (libsource (lib "Resistors") (part "Resistor - 1%"))
    )
    (comp (ref "R123")
      (value "43")
      (footprint "RESC1005X40N")
      (description "Resistor - 1%")
      (fields
        (field (name "MANUFACTURER PART NUMBER") "R0402_43R_1%_0.0625W_100PPM")
        (field (name "MANUFACTURER") "GENERIC")
        (field (name "AUTHOR") "CERN DEM JLC")
      )
      (libsource (lib "Resistors") (part "Resistor - 1%"))
    )
    (comp (ref "R124")
      (value "43")
      (footprint "RESC1005X40N")
      (description "Resistor - 1%")
      (fields
        (field (name "MANUFACTURER PART NUMBER") "R0402_43R_1%_0.0625W_100PPM")
        (field (name "MANUFACTURER") "GENERIC")
        (field (name "AUTHOR") "CERN DEM JLC")
      )
      (libsource (lib "Resistors") (part "Resistor - 1%"))
    )
    (comp (ref "R125")
      (value "43")
      (footprint "RESC1005X40N")
      (description "Resistor - 1%")
      (fields
        (field (name "MANUFACTURER PART NUMBER") "R0402_43R_1%_0.0625W_100PPM")
        (field (name "MANUFACTURER") "GENERIC")
        (field (name "AUTHOR") "CERN DEM JLC")
      )
      (libsource (lib "Resistors") (part "Resistor - 1%"))
    )
    (comp (ref "R126")
      (value "43")
      (footprint "RESC1005X40N")
      (description "Resistor - 1%")
      (fields
        (field (name "MANUFACTURER PART NUMBER") "R0402_43R_1%_0.0625W_100PPM")
        (field (name "MANUFACTURER") "GENERIC")
        (field (name "AUTHOR") "CERN DEM JLC")
      )
      (libsource (lib "Resistors") (part "Resistor - 1%"))
    )
    (comp (ref "R127")
      (value "43")
      (footprint "RESC1005X40N")
      (description "Resistor - 1%")
      (fields
        (field (name "MANUFACTURER PART NUMBER") "R0402_43R_1%_0.0625W_100PPM")
        (field (name "MANUFACTURER") "GENERIC")
        (field (name "AUTHOR") "CERN DEM JLC")
      )
      (libsource (lib "Resistors") (part "Resistor - 1%"))
    )
    (comp (ref "R128")
      (value "43")
      (footprint "RESC1005X40N")
      (description "Resistor - 1%")
      (fields
        (field (name "MANUFACTURER PART NUMBER") "R0402_43R_1%_0.0625W_100PPM")
        (field (name "MANUFACTURER") "GENERIC")
        (field (name "AUTHOR") "CERN DEM JLC")
      )
      (libsource (lib "Resistors") (part "Resistor - 1%"))
    )
    (comp (ref "R129")
      (value "43")
      (footprint "RESC1005X40N")
      (description "Resistor - 1%")
      (fields
        (field (name "MANUFACTURER PART NUMBER") "R0402_43R_1%_0.0625W_100PPM")
        (field (name "MANUFACTURER") "GENERIC")
        (field (name "AUTHOR") "CERN DEM JLC")
      )
      (libsource (lib "Resistors") (part "Resistor - 1%"))
    )
    (comp (ref "R130")
      (value "43")
      (footprint "RESC1005X40N")
      (description "Resistor - 1%")
      (fields
        (field (name "MANUFACTURER PART NUMBER") "R0402_43R_1%_0.0625W_100PPM")
        (field (name "MANUFACTURER") "GENERIC")
        (field (name "AUTHOR") "CERN DEM JLC")
      )
      (libsource (lib "Resistors") (part "Resistor - 1%"))
    )
    (comp (ref "R131")
      (value "43")
      (footprint "RESC1005X40N")
      (description "Resistor - 1%")
      (fields
        (field (name "MANUFACTURER PART NUMBER") "R0402_43R_1%_0.0625W_100PPM")
        (field (name "MANUFACTURER") "GENERIC")
        (field (name "AUTHOR") "CERN DEM JLC")
      )
      (libsource (lib "Resistors") (part "Resistor - 1%"))
    )
    (comp (ref "R132")
      (value "43")
      (footprint "RESC1005X40N")
      (description "Resistor - 1%")
      (fields
        (field (name "MANUFACTURER PART NUMBER") "R0402_43R_1%_0.0625W_100PPM")
        (field (name "MANUFACTURER") "GENERIC")
        (field (name "AUTHOR") "CERN DEM JLC")
      )
      (libsource (lib "Resistors") (part "Resistor - 1%"))
    )
    (comp (ref "R133")
      (value "43")
      (footprint "RESC1005X40N")
      (description "Resistor - 1%")
      (fields
        (field (name "MANUFACTURER PART NUMBER") "R0402_43R_1%_0.0625W_100PPM")
        (field (name "MANUFACTURER") "GENERIC")
        (field (name "AUTHOR") "CERN DEM JLC")
      )
      (libsource (lib "Resistors") (part "Resistor - 1%"))
    )
    (comp (ref "R134")
      (value "43")
      (footprint "RESC1005X40N")
      (description "Resistor - 1%")
      (fields
        (field (name "MANUFACTURER PART NUMBER") "R0402_43R_1%_0.0625W_100PPM")
        (field (name "MANUFACTURER") "GENERIC")
        (field (name "AUTHOR") "CERN DEM JLC")
      )
      (libsource (lib "Resistors") (part "Resistor - 1%"))
    )
    (comp (ref "R135")
      (value "4k7")
      (footprint "RESC1005X40N")
      (description "Resistor - 1%")
      (fields
        (field (name "MANUFACTURER PART NUMBER") "R0402_4K7_1%_0.0625W_100PPM")
        (field (name "MANUFACTURER") "GENERIC")
        (field (name "AUTHOR") "CERN DEM JLC")
      )
      (libsource (lib "Resistors") (part "Resistor - 1%"))
    )
    (comp (ref "R136")
      (value "240")
      (footprint "RESC1005X40N")
      (description "Resistor - 1%")
      (fields
        (field (name "MANUFACTURER PART NUMBER") "R0402_240R_1%_0.0625W_100PPM")
        (field (name "MANUFACTURER") "GENERIC")
        (field (name "AUTHOR") "CERN DEM JLC")
      )
      (libsource (lib "Resistors") (part "Resistor - 1%"))
    )
    (comp (ref "R137")
      (value "240")
      (footprint "RESC1005X40N")
      (description "Resistor - 1%")
      (fields
        (field (name "MANUFACTURER PART NUMBER") "R0402_240R_1%_0.0625W_100PPM")
        (field (name "MANUFACTURER") "GENERIC")
        (field (name "AUTHOR") "CERN DEM JLC")
      )
      (libsource (lib "Resistors") (part "Resistor - 1%"))
    )
    (comp (ref "R138")
      (value "43")
      (footprint "RESC1005X40N")
      (description "Resistor - 1%")
      (fields
        (field (name "MANUFACTURER PART NUMBER") "R0402_43R_1%_0.0625W_100PPM")
        (field (name "MANUFACTURER") "GENERIC")
        (field (name "AUTHOR") "CERN DEM JLC")
      )
      (libsource (lib "Resistors") (part "Resistor - 1%"))
    )
    (comp (ref "R340")
      (value "10k")
      (footprint "RESC1005X40N")
      (description "Resistor - 1%")
      (fields
        (field (name "MANUFACTURER PART NUMBER") "R0402_10K_1%_0.0625W_100PPM")
        (field (name "MANUFACTURER") "GENERIC")
        (field (name "AUTHOR") "CERN DEM JLC")
      )
      (libsource (lib "Resistors") (part "Resistor - 1%"))
    )
  )
  (nets
    (net (code "2") (name "/DDR3_64_A0") (class "Default")
      (node (ref "IC22") (pin "N3") (pinfunction "A0_N3") (pintype "input"))
      (node (ref "IC23") (pin "N3") (pinfunction "A0_N3") (pintype "input"))
      (node (ref "IC25") (pin "N3") (pinfunction "A0_N3") (pintype "input"))
      (node (ref "IC4") (pin "N3") (pinfunction "A0_N3") (pintype "input"))
      (node (ref "R130") (pin "2") (pinfunction "2_2") (pintype "passive"))
    )
    (net (code "3") (name "/DDR3_64_A1") (class "Default")
      (node (ref "IC22") (pin "P7") (pinfunction "A1_P7") (pintype "input"))
      (node (ref "IC23") (pin "P7") (pinfunction "A1_P7") (pintype "input"))
      (node (ref "IC25") (pin "P7") (pinfunction "A1_P7") (pintype "input"))
      (node (ref "IC4") (pin "P7") (pinfunction "A1_P7") (pintype "input"))
      (node (ref "R129") (pin "2") (pinfunction "2_2") (pintype "passive"))
    )
    (net (code "4") (name "/DDR3_64_A2") (class "Default")
      (node (ref "IC22") (pin "P3") (pinfunction "A2_P3") (pintype "input"))
      (node (ref "IC23") (pin "P3") (pinfunction "A2_P3") (pintype "input"))
      (node (ref "IC25") (pin "P3") (pinfunction "A2_P3") (pintype "input"))
      (node (ref "IC4") (pin "P3") (pinfunction "A2_P3") (pintype "input"))
      (node (ref "R128") (pin "2") (pinfunction "2_2") (pintype "passive"))
    )
    (net (code "5") (name "/DDR3_64_A3") (class "Default")
      (node (ref "IC22") (pin "N2") (pinfunction "A3_N2") (pintype "input"))
      (node (ref "IC23") (pin "N2") (pinfunction "A3_N2") (pintype "input"))
      (node (ref "IC25") (pin "N2") (pinfunction "A3_N2") (pintype "input"))
      (node (ref "IC4") (pin "N2") (pinfunction "A3_N2") (pintype "input"))
      (node (ref "R134") (pin "2") (pinfunction "2_2") (pintype "passive"))
    )
    (net (code "6") (name "/DDR3_64_A4") (class "Default")
      (node (ref "IC22") (pin "P8") (pinfunction "A4_P8") (pintype "input"))
      (node (ref "IC23") (pin "P8") (pinfunction "A4_P8") (pintype "input"))
      (node (ref "IC25") (pin "P8") (pinfunction "A4_P8") (pintype "input"))
      (node (ref "IC4") (pin "P8") (pinfunction "A4_P8") (pintype "input"))
      (node (ref "R133") (pin "2") (pinfunction "2_2") (pintype "passive"))
    )
    (net (code "7") (name "/DDR3_64_A5") (class "Default")
      (node (ref "IC22") (pin "P2") (pinfunction "A5_P2") (pintype "input"))
      (node (ref "IC23") (pin "P2") (pinfunction "A5_P2") (pintype "input"))
      (node (ref "IC25") (pin "P2") (pinfunction "A5_P2") (pintype "input"))
      (node (ref "IC4") (pin "P2") (pinfunction "A5_P2") (pintype "input"))
      (node (ref "R132") (pin "2") (pinfunction "2_2") (pintype "passive"))
    )
    (net (code "8") (name "/DDR3_64_A6") (class "Default")
      (node (ref "IC22") (pin "R8") (pinfunction "A6_R8") (pintype "input"))
      (node (ref "IC23") (pin "R8") (pinfunction "A6_R8") (pintype "input"))
      (node (ref "IC25") (pin "R8") (pinfunction "A6_R8") (pintype "input"))
      (node (ref "IC4") (pin "R8") (pinfunction "A6_R8") (pintype "input"))
      (node (ref "R131") (pin "2") (pinfunction "2_2") (pintype "passive"))
    )
    (net (code "9") (name "/DDR3_64_A7") (class "Default")
      (node (ref "IC22") (pin "R2") (pinfunction "A7_R2") (pintype "input"))
      (node (ref "IC23") (pin "R2") (pinfunction "A7_R2") (pintype "input"))
      (node (ref "IC25") (pin "R2") (pinfunction "A7_R2") (pintype "input"))
      (node (ref "IC4") (pin "R2") (pinfunction "A7_R2") (pintype "input"))
      (node (ref "R127") (pin "2") (pinfunction "2_2") (pintype "passive"))
    )
    (net (code "10") (name "/DDR3_64_A8") (class "Default")
      (node (ref "IC22") (pin "T8") (pinfunction "A8_T8") (pintype "input"))
      (node (ref "IC23") (pin "T8") (pinfunction "A8_T8") (pintype "input"))
      (node (ref "IC25") (pin "T8") (pinfunction "A8_T8") (pintype "input"))
      (node (ref "IC4") (pin "T8") (pinfunction "A8_T8") (pintype "input"))
      (node (ref "R126") (pin "2") (pinfunction "2_2") (pintype "passive"))
    )
    (net (code "11") (name "/DDR3_64_A9") (class "Default")
      (node (ref "IC22") (pin "R3") (pinfunction "A9_R3") (pintype "input"))
      (node (ref "IC23") (pin "R3") (pinfunction "A9_R3") (pintype "input"))
      (node (ref "IC25") (pin "R3") (pinfunction "A9_R3") (pintype "input"))
      (node (ref "IC4") (pin "R3") (pinfunction "A9_R3") (pintype "input"))
      (node (ref "R125") (pin "2") (pinfunction "2_2") (pintype "passive"))
    )
    (net (code "12") (name "/DDR3_64_A10") (class "Default")
      (node (ref "IC22") (pin "L7") (pinfunction "A10/AP_L7") (pintype "input"))
      (node (ref "IC23") (pin "L7") (pinfunction "A10/AP_L7") (pintype "input"))
      (node (ref "IC25") (pin "L7") (pinfunction "A10/AP_L7") (pintype "input"))
      (node (ref "IC4") (pin "L7") (pinfunction "A10/AP_L7") (pintype "input"))
      (node (ref "R124") (pin "2") (pinfunction "2_2") (pintype "passive"))
    )
    (net (code "13") (name "/DDR3_64_A11") (class "Default")
      (node (ref "IC22") (pin "R7") (pinfunction "A11_R7") (pintype "input"))
      (node (ref "IC23") (pin "R7") (pinfunction "A11_R7") (pintype "input"))
      (node (ref "IC25") (pin "R7") (pinfunction "A11_R7") (pintype "input"))
      (node (ref "IC4") (pin "R7") (pinfunction "A11_R7") (pintype "input"))
      (node (ref "R123") (pin "2") (pinfunction "2_2") (pintype "passive"))
    )
    (net (code "14") (name "/DDR3_64_A12") (class "Default")
      (node (ref "IC22") (pin "N7") (pinfunction "A12/~{BC}_N7") (pintype "input"))
      (node (ref "IC23") (pin "N7") (pinfunction "A12/~{BC}_N7") (pintype "input"))
      (node (ref "IC25") (pin "N7") (pinfunction "A12/~{BC}_N7") (pintype "input"))
      (node (ref "IC4") (pin "N7") (pinfunction "A12/~{BC}_N7") (pintype "input"))
      (node (ref "R122") (pin "2") (pinfunction "2_2") (pintype "passive"))
    )
    (net (code "15") (name "/DDR3_64_A13") (class "Default")
      (node (ref "IC22") (pin "T3") (pinfunction "A13_T3") (pintype "input"))
      (node (ref "IC23") (pin "T3") (pinfunction "A13_T3") (pintype "input"))
      (node (ref "IC25") (pin "T3") (pinfunction "A13_T3") (pintype "input"))
      (node (ref "IC4") (pin "T3") (pinfunction "A13_T3") (pintype "input"))
      (node (ref "R121") (pin "2") (pinfunction "2_2") (pintype "passive"))
    )
    (net (code "16") (name "/DDR3_64_A14") (class "Default")
      (node (ref "IC22") (pin "T7") (pinfunction "A14_T7") (pintype "passive"))
      (node (ref "IC23") (pin "T7") (pinfunction "A14_T7") (pintype "passive"))
      (node (ref "IC25") (pin "T7") (pinfunction "A14_T7") (pintype "passive"))
      (node (ref "IC4") (pin "T7") (pinfunction "A14_T7") (pintype "passive"))
      (node (ref "R138") (pin "2") (pinfunction "2_2") (pintype "passive"))
    )
    (net (code "17") (name "/DDR3_64_BA0") (class "Default")
      (node (ref "IC22") (pin "M2") (pinfunction "BA0_M2") (pintype "input"))
      (node (ref "IC23") (pin "M2") (pinfunction "BA0_M2") (pintype "input"))
      (node (ref "IC25") (pin "M2") (pinfunction "BA0_M2") (pintype "input"))
      (node (ref "IC4") (pin "M2") (pinfunction "BA0_M2") (pintype "input"))
      (node (ref "R112") (pin "2") (pinfunction "2_2") (pintype "passive"))
    )
    (net (code "18") (name "/DDR3_64_BA1") (class "Default")
      (node (ref "IC22") (pin "N8") (pinfunction "BA1_N8") (pintype "input"))
      (node (ref "IC23") (pin "N8") (pinfunction "BA1_N8") (pintype "input"))
      (node (ref "IC25") (pin "N8") (pinfunction "BA1_N8") (pintype "input"))
      (node (ref "IC4") (pin "N8") (pinfunction "BA1_N8") (pintype "input"))
      (node (ref "R111") (pin "2") (pinfunction "2_2") (pintype "passive"))
    )
    (net (code "19") (name "/DDR3_64_BA2") (class "Default")
      (node (ref "IC22") (pin "M3") (pinfunction "BA2_M3") (pintype "input"))
      (node (ref "IC23") (pin "M3") (pinfunction "BA2_M3") (pintype "input"))
      (node (ref "IC25") (pin "M3") (pinfunction "BA2_M3") (pintype "input"))
      (node (ref "IC4") (pin "M3") (pinfunction "BA2_M3") (pintype "input"))
      (node (ref "R110") (pin "2") (pinfunction "2_2") (pintype "passive"))
    )
    (net (code "21") (name "/DDR3_64_CAS_N") (class "Default")
      (node (ref "IC22") (pin "K3") (pinfunction "~{CAS}_K3") (pintype "input"))
      (node (ref "IC23") (pin "K3") (pinfunction "~{CAS}_K3") (pintype "input"))
      (node (ref "IC25") (pin "K3") (pinfunction "~{CAS}_K3") (pintype "input"))
      (node (ref "IC4") (pin "K3") (pinfunction "~{CAS}_K3") (pintype "input"))
      (node (ref "R116") (pin "2") (pinfunction "2_2") (pintype "passive"))
    )
    (net (code "22") (name "/DDR3_64_CKE") (class "Default")
      (node (ref "IC22") (pin "K9") (pinfunction "CKE_K9") (pintype "input"))
      (node (ref "IC23") (pin "K9") (pinfunction "CKE_K9") (pintype "input"))
      (node (ref "IC25") (pin "K9") (pinfunction "CKE_K9") (pintype "input"))
      (node (ref "IC4") (pin "K9") (pinfunction "CKE_K9") (pintype "input"))
      (node (ref "R118") (pin "2") (pinfunction "2_2") (pintype "passive"))
    )
    (net (code "23") (name "/DDR3_64_CK_N") (class "Default")
      (node (ref "IC22") (pin "K7") (pinfunction "~{CK}_K7") (pintype "input"))
      (node (ref "IC23") (pin "K7") (pinfunction "~{CK}_K7") (pintype "input"))
      (node (ref "IC25") (pin "K7") (pinfunction "~{CK}_K7") (pintype "input"))
      (node (ref "IC4") (pin "K7") (pinfunction "~{CK}_K7") (pintype "input"))
      (node (ref "R119") (pin "2") (pinfunction "2_2") (pintype "passive"))
    )
    (net (code "24") (name "/DDR3_64_CK_P") (class "Default")
      (node (ref "IC22") (pin "J7") (pinfunction "CK_J7") (pintype "input"))
      (node (ref "IC23") (pin "J7") (pinfunction "CK_J7") (pintype "input"))
      (node (ref "IC25") (pin "J7") (pinfunction "CK_J7") (pintype "input"))
      (node (ref "IC4") (pin "J7") (pinfunction "CK_J7") (pintype "input"))
      (node (ref "R120") (pin "2") (pinfunction "2_2") (pintype "passive"))
    )
    (net (code "25") (name "/DDR3_64_CS_N") (class "Default")
      (node (ref "IC22") (pin "L2") (pinfunction "~{CS}_L2") (pintype "input"))
      (node (ref "IC23") (pin "L2") (pinfunction "~{CS}_L2") (pintype "input"))
      (node (ref "IC25") (pin "L2") (pinfunction "~{CS}_L2") (pintype "input"))
      (node (ref "IC4") (pin "L2") (pinfunction "~{CS}_L2") (pintype "input"))
      (node (ref "R115") (pin "2") (pinfunction "2_2") (pintype "passive"))
    )
    (net (code "26") (name "/DDR3_64_DM0") (class "Default")
      (node (ref "IC22") (pin "E7") (pinfunction "LDM_E7") (pintype "input"))
    )
    (net (code "27") (name "/DDR3_64_DM1") (class "Default")
      (node (ref "IC22") (pin "D3") (pinfunction "UDM_D3") (pintype "input"))
    )
    (net (code "28") (name "/DDR3_64_DM2") (class "Default")
      (node (ref "IC23") (pin "E7") (pinfunction "LDM_E7") (pintype "input"))
    )
    (net (code "29") (name "/DDR3_64_DM3") (class "Default")
      (node (ref "IC23") (pin "D3") (pinfunction "UDM_D3") (pintype "input"))
    )
    (net (code "30") (name "/DDR3_64_DM4") (class "Default")
      (node (ref "IC4") (pin "E7") (pinfunction "LDM_E7") (pintype "input"))
    )
    (net (code "31") (name "/DDR3_64_DM5") (class "Default")
      (node (ref "IC4") (pin "D3") (pinfunction "UDM_D3") (pintype "input"))
    )
    (net (code "32") (name "/DDR3_64_DM6") (class "Default")
      (node (ref "IC25") (pin "E7") (pinfunction "LDM_E7") (pintype "input"))
    )
    (net (code "33") (name "/DDR3_64_DM7") (class "Default")
      (node (ref "IC25") (pin "D3") (pinfunction "UDM_D3") (pintype "input"))
    )
    (net (code "35") (name "/DDR3_64_DQ0") (class "Default")
      (node (ref "IC22") (pin "E3") (pinfunction "DQ0_E3") (pintype "bidirectional"))
    )
    (net (code "36") (name "/DDR3_64_DQ1") (class "Default")
      (node (ref "IC22") (pin "F7") (pinfunction "DQ1_F7") (pintype "bidirectional"))
    )
    (net (code "37") (name "/DDR3_64_DQ2") (class "Default")
      (node (ref "IC22") (pin "F2") (pinfunction "DQ2_F2") (pintype "bidirectional"))
    )
    (net (code "38") (name "/DDR3_64_DQ3") (class "Default")
      (node (ref "IC22") (pin "F8") (pinfunction "DQ3_F8") (pintype "bidirectional"))
    )
    (net (code "39") (name "/DDR3_64_DQ4") (class "Default")
      (node (ref "IC22") (pin "H3") (pinfunction "DQ4_H3") (pintype "bidirectional"))
    )
    (net (code "40") (name "/DDR3_64_DQ5") (class "Default")
      (node (ref "IC22") (pin "H8") (pinfunction "DQ5_H8") (pintype "bidirectional"))
    )
    (net (code "41") (name "/DDR3_64_DQ6") (class "Default")
      (node (ref "IC22") (pin "G2") (pinfunction "DQ6_G2") (pintype "bidirectional"))
    )
    (net (code "42") (name "/DDR3_64_DQ7") (class "Default")
      (node (ref "IC22") (pin "H7") (pinfunction "DQ7_H7") (pintype "bidirectional"))
    )
    (net (code "43") (name "/DDR3_64_DQ8") (class "Default")
      (node (ref "IC22") (pin "D7") (pinfunction "DQ8_D7") (pintype "bidirectional"))
    )
    (net (code "44") (name "/DDR3_64_DQ9") (class "Default")
      (node (ref "IC22") (pin "C3") (pinfunction "DQ9_C3") (pintype "bidirectional"))
    )
    (net (code "45") (name "/DDR3_64_DQ10") (class "Default")
      (node (ref "IC22") (pin "C8") (pinfunction "DQ10_C8") (pintype "bidirectional"))
    )
    (net (code "46") (name "/DDR3_64_DQ11") (class "Default")
      (node (ref "IC22") (pin "C2") (pinfunction "DQ11_C2") (pintype "bidirectional"))
    )
    (net (code "47") (name "/DDR3_64_DQ12") (class "Default")
      (node (ref "IC22") (pin "A7") (pinfunction "DQ12_A7") (pintype "bidirectional"))
    )
    (net (code "48") (name "/DDR3_64_DQ13") (class "Default")
      (node (ref "IC22") (pin "A2") (pinfunction "DQ13_A2") (pintype "bidirectional"))
    )
    (net (code "49") (name "/DDR3_64_DQ14") (class "Default")
      (node (ref "IC22") (pin "B8") (pinfunction "DQ14_B8") (pintype "bidirectional"))
    )
    (net (code "50") (name "/DDR3_64_DQ15") (class "Default")
      (node (ref "IC22") (pin "A3") (pinfunction "DQ15_A3") (pintype "bidirectional"))
    )
    (net (code "51") (name "/DDR3_64_DQ16") (class "Default")
      (node (ref "IC23") (pin "E3") (pinfunction "DQ0_E3") (pintype "bidirectional"))
    )
    (net (code "52") (name "/DDR3_64_DQ17") (class "Default")
      (node (ref "IC23") (pin "F7") (pinfunction "DQ1_F7") (pintype "bidirectional"))
    )
    (net (code "53") (name "/DDR3_64_DQ18") (class "Default")
      (node (ref "IC23") (pin "F2") (pinfunction "DQ2_F2") (pintype "bidirectional"))
    )
    (net (code "54") (name "/DDR3_64_DQ19") (class "Default")
      (node (ref "IC23") (pin "F8") (pinfunction "DQ3_F8") (pintype "bidirectional"))
    )
    (net (code "55") (name "/DDR3_64_DQ20") (class "Default")
      (node (ref "IC23") (pin "H3") (pinfunction "DQ4_H3") (pintype "bidirectional"))
    )
    (net (code "56") (name "/DDR3_64_DQ21") (class "Default")
      (node (ref "IC23") (pin "H8") (pinfunction "DQ5_H8") (pintype "bidirectional"))
    )
    (net (code "57") (name "/DDR3_64_DQ22") (class "Default")
      (node (ref "IC23") (pin "G2") (pinfunction "DQ6_G2") (pintype "bidirectional"))
    )
    (net (code "58") (name "/DDR3_64_DQ23") (class "Default")
      (node (ref "IC23") (pin "H7") (pinfunction "DQ7_H7") (pintype "bidirectional"))
    )
    (net (code "59") (name "/DDR3_64_DQ24") (class "Default")
      (node (ref "IC23") (pin "D7") (pinfunction "DQ8_D7") (pintype "bidirectional"))
    )
    (net (code "60") (name "/DDR3_64_DQ25") (class "Default")
      (node (ref "IC23") (pin "C3") (pinfunction "DQ9_C3") (pintype "bidirectional"))
    )
    (net (code "61") (name "/DDR3_64_DQ26") (class "Default")
      (node (ref "IC23") (pin "C8") (pinfunction "DQ10_C8") (pintype "bidirectional"))
    )
    (net (code "62") (name "/DDR3_64_DQ27") (class "Default")
      (node (ref "IC23") (pin "C2") (pinfunction "DQ11_C2") (pintype "bidirectional"))
    )
    (net (code "63") (name "/DDR3_64_DQ28") (class "Default")
      (node (ref "IC23") (pin "A7") (pinfunction "DQ12_A7") (pintype "bidirectional"))
    )
    (net (code "64") (name "/DDR3_64_DQ29") (class "Default")
      (node (ref "IC23") (pin "A2") (pinfunction "DQ13_A2") (pintype "bidirectional"))
    )
    (net (code "65") (name "/DDR3_64_DQ30") (class "Default")
      (node (ref "IC23") (pin "B8") (pinfunction "DQ14_B8") (pintype "bidirectional"))
    )
    (net (code "66") (name "/DDR3_64_DQ31") (class "Default")
      (node (ref "IC23") (pin "A3") (pinfunction "DQ15_A3") (pintype "bidirectional"))
    )
    (net (code "67") (name "/DDR3_64_DQ32") (class "Default")
      (node (ref "IC4") (pin "E3") (pinfunction "DQ0_E3") (pintype "bidirectional"))
    )
    (net (code "68") (name "/DDR3_64_DQ33") (class "Default")
      (node (ref "IC4") (pin "F7") (pinfunction "DQ1_F7") (pintype "bidirectional"))
    )
    (net (code "69") (name "/DDR3_64_DQ34") (class "Default")
      (node (ref "IC4") (pin "F2") (pinfunction "DQ2_F2") (pintype "bidirectional"))
    )
    (net (code "70") (name "/DDR3_64_DQ35") (class "Default")
      (node (ref "IC4") (pin "F8") (pinfunction "DQ3_F8") (pintype "bidirectional"))
    )
    (net (code "71") (name "/DDR3_64_DQ36") (class "Default")
      (node (ref "IC4") (pin "H3") (pinfunction "DQ4_H3") (pintype "bidirectional"))
    )
    (net (code "72") (name "/DDR3_64_DQ37") (class "Default")
      (node (ref "IC4") (pin "H8") (pinfunction "DQ5_H8") (pintype "bidirectional"))
    )
    (net (code "73") (name "/DDR3_64_DQ38") (class "Default")
      (node (ref "IC4") (pin "G2") (pinfunction "DQ6_G2") (pintype "bidirectional"))
    )
    (net (code "74") (name "/DDR3_64_DQ39") (class "Default")
      (node (ref "IC4") (pin "H7") (pinfunction "DQ7_H7") (pintype "bidirectional"))
    )
    (net (code "75") (name "/DDR3_64_DQ40") (class "Default")
      (node (ref "IC4") (pin "D7") (pinfunction "DQ8_D7") (pintype "bidirectional"))
    )
    (net (code "76") (name "/DDR3_64_DQ41") (class "Default")
      (node (ref "IC4") (pin "C3") (pinfunction "DQ9_C3") (pintype "bidirectional"))
    )
    (net (code "77") (name "/DDR3_64_DQ42") (class "Default")
      (node (ref "IC4") (pin "C8") (pinfunction "DQ10_C8") (pintype "bidirectional"))
    )
    (net (code "78") (name "/DDR3_64_DQ43") (class "Default")
      (node (ref "IC4") (pin "C2") (pinfunction "DQ11_C2") (pintype "bidirectional"))
    )
    (net (code "79") (name "/DDR3_64_DQ44") (class "Default")
      (node (ref "IC4") (pin "A7") (pinfunction "DQ12_A7") (pintype "bidirectional"))
    )
    (net (code "80") (name "/DDR3_64_DQ45") (class "Default")
      (node (ref "IC4") (pin "A2") (pinfunction "DQ13_A2") (pintype "bidirectional"))
    )
    (net (code "81") (name "/DDR3_64_DQ46") (class "Default")
      (node (ref "IC4") (pin "B8") (pinfunction "DQ14_B8") (pintype "bidirectional"))
    )
    (net (code "82") (name "/DDR3_64_DQ47") (class "Default")
      (node (ref "IC4") (pin "A3") (pinfunction "DQ15_A3") (pintype "bidirectional"))
    )
    (net (code "83") (name "/DDR3_64_DQ48") (class "Default")
      (node (ref "IC25") (pin "E3") (pinfunction "DQ0_E3") (pintype "bidirectional"))
    )
    (net (code "84") (name "/DDR3_64_DQ49") (class "Default")
      (node (ref "IC25") (pin "F7") (pinfunction "DQ1_F7") (pintype "bidirectional"))
    )
    (net (code "85") (name "/DDR3_64_DQ50") (class "Default")
      (node (ref "IC25") (pin "F2") (pinfunction "DQ2_F2") (pintype "bidirectional"))
    )
    (net (code "86") (name "/DDR3_64_DQ51") (class "Default")
      (node (ref "IC25") (pin "F8") (pinfunction "DQ3_F8") (pintype "bidirectional"))
    )
    (net (code "87") (name "/DDR3_64_DQ52") (class "Default")
      (node (ref "IC25") (pin "H3") (pinfunction "DQ4_H3") (pintype "bidirectional"))
    )
    (net (code "88") (name "/DDR3_64_DQ53") (class "Default")
      (node (ref "IC25") (pin "H8") (pinfunction "DQ5_H8") (pintype "bidirectional"))
    )
    (net (code "89") (name "/DDR3_64_DQ54") (class "Default")
      (node (ref "IC25") (pin "G2") (pinfunction "DQ6_G2") (pintype "bidirectional"))
    )
    (net (code "90") (name "/DDR3_64_DQ55") (class "Default")
      (node (ref "IC25") (pin "H7") (pinfunction "DQ7_H7") (pintype "bidirectional"))
    )
    (net (code "91") (name "/DDR3_64_DQ56") (class "Default")
      (node (ref "IC25") (pin "D7") (pinfunction "DQ8_D7") (pintype "bidirectional"))
    )
    (net (code "92") (name "/DDR3_64_DQ57") (class "Default")
      (node (ref "IC25") (pin "C3") (pinfunction "DQ9_C3") (pintype "bidirectional"))
    )
    (net (code "93") (name "/DDR3_64_DQ58") (class "Default")
      (node (ref "IC25") (pin "C8") (pinfunction "DQ10_C8") (pintype "bidirectional"))
    )
    (net (code "94") (name "/DDR3_64_DQ59") (class "Default")
      (node (ref "IC25") (pin "C2") (pinfunction "DQ11_C2") (pintype "bidirectional"))
    )
    (net (code "95") (name "/DDR3_64_DQ60") (class "Default")
      (node (ref "IC25") (pin "A7") (pinfunction "DQ12_A7") (pintype "bidirectional"))
    )
    (net (code "96") (name "/DDR3_64_DQ61") (class "Default")
      (node (ref "IC25") (pin "A2") (pinfunction "DQ13_A2") (pintype "bidirectional"))
    )
    (net (code "97") (name "/DDR3_64_DQ62") (class "Default")
      (node (ref "IC25") (pin "B8") (pinfunction "DQ14_B8") (pintype "bidirectional"))
    )
    (net (code "98") (name "/DDR3_64_DQ63") (class "Default")
      (node (ref "IC25") (pin "A3") (pinfunction "DQ15_A3") (pintype "bidirectional"))
    )
    (net (code "99") (name "/DDR3_64_DQS0_N") (class "Default")
      (node (ref "IC22") (pin "G3") (pinfunction "~{LDQS}_G3") (pintype "bidirectional"))
    )
    (net (code "100") (name "/DDR3_64_DQS0_P") (class "Default")
      (node (ref "IC22") (pin "F3") (pinfunction "LDQS_F3") (pintype "bidirectional"))
    )
    (net (code "101") (name "/DDR3_64_DQS1_N") (class "Default")
      (node (ref "IC22") (pin "B7") (pinfunction "~{UDQS}_B7") (pintype "bidirectional"))
    )
    (net (code "102") (name "/DDR3_64_DQS1_P") (class "Default")
      (node (ref "IC22") (pin "C7") (pinfunction "UDQS_C7") (pintype "bidirectional"))
    )
    (net (code "103") (name "/DDR3_64_DQS2_N") (class "Default")
      (node (ref "IC23") (pin "G3") (pinfunction "~{LDQS}_G3") (pintype "bidirectional"))
    )
    (net (code "104") (name "/DDR3_64_DQS2_P") (class "Default")
      (node (ref "IC23") (pin "F3") (pinfunction "LDQS_F3") (pintype "bidirectional"))
    )
    (net (code "105") (name "/DDR3_64_DQS3_N") (class "Default")
      (node (ref "IC23") (pin "B7") (pinfunction "~{UDQS}_B7") (pintype "bidirectional"))
    )
    (net (code "106") (name "/DDR3_64_DQS3_P") (class "Default")
      (node (ref "IC23") (pin "C7") (pinfunction "UDQS_C7") (pintype "bidirectional"))
    )
    (net (code "107") (name "/DDR3_64_DQS4_N") (class "Default")
      (node (ref "IC4") (pin "G3") (pinfunction "~{LDQS}_G3") (pintype "bidirectional"))
    )
    (net (code "108") (name "/DDR3_64_DQS4_P") (class "Default")
      (node (ref "IC4") (pin "F3") (pinfunction "LDQS_F3") (pintype "bidirectional"))
    )
    (net (code "109") (name "/DDR3_64_DQS5_N") (class "Default")
      (node (ref "IC4") (pin "B7") (pinfunction "~{UDQS}_B7") (pintype "bidirectional"))
    )
    (net (code "110") (name "/DDR3_64_DQS5_P") (class "Default")
      (node (ref "IC4") (pin "C7") (pinfunction "UDQS_C7") (pintype "bidirectional"))
    )
    (net (code "111") (name "/DDR3_64_DQS6_N") (class "Default")
      (node (ref "IC25") (pin "G3") (pinfunction "~{LDQS}_G3") (pintype "bidirectional"))
    )
    (net (code "112") (name "/DDR3_64_DQS6_P") (class "Default")
      (node (ref "IC25") (pin "F3") (pinfunction "LDQS_F3") (pintype "bidirectional"))
    )
    (net (code "113") (name "/DDR3_64_DQS7_N") (class "Default")
      (node (ref "IC25") (pin "B7") (pinfunction "~{UDQS}_B7") (pintype "bidirectional"))
    )
    (net (code "114") (name "/DDR3_64_DQS7_P") (class "Default")
      (node (ref "IC25") (pin "C7") (pinfunction "UDQS_C7") (pintype "bidirectional"))
    )
    (net (code "116") (name "/DDR3_64_ODT") (class "Default")
      (node (ref "IC22") (pin "K1") (pinfunction "ODT_K1") (pintype "input"))
      (node (ref "IC23") (pin "K1") (pinfunction "ODT_K1") (pintype "input"))
      (node (ref "IC25") (pin "K1") (pinfunction "ODT_K1") (pintype "input"))
      (node (ref "IC4") (pin "K1") (pinfunction "ODT_K1") (pintype "input"))
      (node (ref "R113") (pin "2") (pinfunction "2_2") (pintype "passive"))
    )
    (net (code "117") (name "/DDR3_64_RAS_N") (class "Default")
      (node (ref "IC22") (pin "J3") (pinfunction "~{RAS}_J3") (pintype "input"))
      (node (ref "IC23") (pin "J3") (pinfunction "~{RAS}_J3") (pintype "input"))
      (node (ref "IC25") (pin "J3") (pinfunction "~{RAS}_J3") (pintype "input"))
      (node (ref "IC4") (pin "J3") (pinfunction "~{RAS}_J3") (pintype "input"))
      (node (ref "R117") (pin "2") (pinfunction "2_2") (pintype "passive"))
    )
    (net (code "118") (name "/DDR3_64_RST_N") (class "Default")
      (node (ref "IC22") (pin "T2") (pinfunction "~{RESET}_T2") (pintype "input"))
      (node (ref "IC23") (pin "T2") (pinfunction "~{RESET}_T2") (pintype "input"))
      (node (ref "IC25") (pin "T2") (pinfunction "~{RESET}_T2") (pintype "input"))
      (node (ref "IC4") (pin "T2") (pinfunction "~{RESET}_T2") (pintype "input"))
      (node (ref "R135") (pin "2") (pinfunction "2_2") (pintype "passive"))
    )
    (net (code "119") (name "/DDR3_64_VREF") (class "Default")
      (node (ref "C79") (pin "1") (pinfunction "1_1") (pintype "passive"))
      (node (ref "C80") (pin "1") (pinfunction "1_1") (pintype "passive"))
      (node (ref "C82") (pin "1") (pinfunction "1_1") (pintype "passive"))
      (node (ref "C83") (pin "1") (pinfunction "1_1") (pintype "passive"))
      (node (ref "C84") (pin "2") (pinfunction "2_2") (pintype "passive"))
      (node (ref "C85") (pin "1") (pinfunction "1_1") (pintype "passive"))
      (node (ref "C86") (pin "1") (pinfunction "1_1") (pintype "passive"))
      (node (ref "C87") (pin "1") (pinfunction "1_1") (pintype "passive"))
      (node (ref "C88") (pin "1") (pinfunction "1_1") (pintype "passive"))
      (node (ref "IC22") (pin "H1") (pinfunction "VREFDQ_H1") (pintype "power_in"))
      (node (ref "IC22") (pin "M8") (pinfunction "VREFCA_M8") (pintype "power_in"))
      (node (ref "IC23") (pin "H1") (pinfunction "VREFDQ_H1") (pintype "power_in"))
      (node (ref "IC23") (pin "M8") (pinfunction "VREFCA_M8") (pintype "power_in"))
      (node (ref "IC25") (pin "H1") (pinfunction "VREFDQ_H1") (pintype "power_in"))
      (node (ref "IC25") (pin "M8") (pinfunction "VREFCA_M8") (pintype "power_in"))
      (node (ref "IC28") (pin "6") (pinfunction "REFOUT_6") (pintype "output"))
      (node (ref "IC4") (pin "H1") (pinfunction "VREFDQ_H1") (pintype "power_in"))
      (node (ref "IC4") (pin "M8") (pinfunction "VREFCA_M8") (pintype "power_in"))
    )
    (net (code "120") (name "/DDR3_64_WE_N") (class "Default")
      (node (ref "IC22") (pin "L3") (pinfunction "~{WE}_L3") (pintype "input"))
      (node (ref "IC23") (pin "L3") (pinfunction "~{WE}_L3") (pintype "input"))
      (node (ref "IC25") (pin "L3") (pinfunction "~{WE}_L3") (pintype "input"))
      (node (ref "IC4") (pin "L3") (pinfunction "~{WE}_L3") (pintype "input"))
      (node (ref "R114") (pin "2") (pinfunction "2_2") (pintype "passive"))
    )
    (net (code "121") (name "/PGOOD") (class "Default")
      (node (ref "IC28") (pin "9") (pinfunction "PGOOD_9") (pintype "output"))
    )
    (net (code "122") (name "/REFIN") (class "Default")
      (node (ref "C425") (pin "2") (pinfunction "2_2") (pintype "passive"))
      (node (ref "IC28") (pin "1") (pinfunction "REFIN_1") (pintype "input"))
      (node (ref "R106") (pin "2") (pinfunction "2_2") (pintype "passive"))
      (node (ref "R340") (pin "2") (pinfunction "2_2") (pintype "passive"))
    )
    (net (code "124") (name "/VOSNS") (class "Default")
      (node (ref "C424") (pin "2") (pinfunction "2_2") (pintype "passive"))
      (node (ref "IC28") (pin "5") (pinfunction "VOSNS_5") (pintype "input"))
      (node (ref "R107") (pin "1") (pinfunction "1_1") (pintype "passive"))
    )
    (net (code "125") (name "/ZQ2") (class "Default")
      (node (ref "IC22") (pin "L8") (pinfunction "ZQ_L8") (pintype "input"))
      (node (ref "R109") (pin "2") (pinfunction "2_2") (pintype "passive"))
    )
    (net (code "127") (name "GND") (class "Default")
      (node (ref "C100") (pin "2") (pinfunction "2_2") (pintype "passive"))
      (node (ref "C101") (pin "2") (pinfunction "2_2") (pintype "passive"))
      (node (ref "C102") (pin "2") (pinfunction "2_2") (pintype "passive"))
      (node (ref "C103") (pin "2") (pinfunction "2_2") (pintype "passive"))
      (node (ref "C104") (pin "2") (pinfunction "2_2") (pintype "passive"))
      (node (ref "C105") (pin "2") (pinfunction "2_2") (pintype "passive"))
      (node (ref "C106") (pin "2") (pinfunction "2_2") (pintype "passive"))
      (node (ref "C107") (pin "2") (pinfunction "2_2") (pintype "passive"))
      (node (ref "C108") (pin "2") (pinfunction "2_2") (pintype "passive"))
      (node (ref "C109") (pin "2") (pinfunction "2_2") (pintype "passive"))
      (node (ref "C110") (pin "2") (pinfunction "2_2") (pintype "passive"))
      (node (ref "C111") (pin "2") (pinfunction "2_2") (pintype "passive"))
      (node (ref "C112") (pin "1") (pinfunction "1_1") (pintype "passive"))
      (node (ref "C275") (pin "2") (pinfunction "2_2") (pintype "passive"))
      (node (ref "C278") (pin "2") (pinfunction "2_2") (pintype "passive"))
      (node (ref "C343") (pin "2") (pinfunction "2_2") (pintype "passive"))
      (node (ref "C354") (pin "2") (pinfunction "2_2") (pintype "passive"))
      (node (ref "C355") (pin "2") (pinfunction "2_2") (pintype "passive"))
      (node (ref "C424") (pin "1") (pinfunction "1_1") (pintype "passive"))
      (node (ref "C425") (pin "1") (pinfunction "1_1") (pintype "passive"))
      (node (ref "C426") (pin "2") (pinfunction "2_2") (pintype "passive"))
      (node (ref "C427") (pin "2") (pinfunction "2_2") (pintype "passive"))
      (node (ref "C428") (pin "2") (pinfunction "2_2") (pintype "passive"))
      (node (ref "C429") (pin "2") (pinfunction "2_2") (pintype "passive"))
      (node (ref "C430") (pin "2") (pinfunction "2_2") (pintype "passive"))
      (node (ref "C431") (pin "2") (pinfunction "2_2") (pintype "passive"))
      (node (ref "C432") (pin "2") (pinfunction "2_2") (pintype "passive"))
      (node (ref "C433") (pin "2") (pinfunction "2_2") (pintype "passive"))
      (node (ref "C434") (pin "2") (pinfunction "2_2") (pintype "passive"))
      (node (ref "C435") (pin "2") (pinfunction "2_2") (pintype "passive"))
      (node (ref "C436") (pin "2") (pinfunction "2_2") (pintype "passive"))
      (node (ref "C44") (pin "2") (pinfunction "2_2") (pintype "passive"))
      (node (ref "C45") (pin "2") (pinfunction "2_2") (pintype "passive"))
      (node (ref "C46") (pin "2") (pinfunction "2_2") (pintype "passive"))
      (node (ref "C47") (pin "2") (pinfunction "2_2") (pintype "passive"))
      (node (ref "C48") (pin "2") (pinfunction "2_2") (pintype "passive"))
      (node (ref "C49") (pin "2") (pinfunction "2_2") (pintype "passive"))
      (node (ref "C50") (pin "2") (pinfunction "2_2") (pintype "passive"))
      (node (ref "C51") (pin "2") (pinfunction "2_2") (pintype "passive"))
      (node (ref "C52") (pin "2") (pinfunction "2_2") (pintype "passive"))
      (node (ref "C53") (pin "2") (pinfunction "2_2") (pintype "passive"))
      (node (ref "C54") (pin "2") (pinfunction "2_2") (pintype "passive"))
      (node (ref "C55") (pin "2") (pinfunction "2_2") (pintype "passive"))
      (node (ref "C56") (pin "2") (pinfunction "2_2") (pintype "passive"))
      (node (ref "C57") (pin "2") (pinfunction "2_2") (pintype "passive"))
      (node (ref "C58") (pin "2") (pinfunction "2_2") (pintype "passive"))
      (node (ref "C59") (pin "2") (pinfunction "2_2") (pintype "passive"))
      (node (ref "C60") (pin "2") (pinfunction "2_2") (pintype "passive"))
      (node (ref "C61") (pin "2") (pinfunction "2_2") (pintype "passive"))
      (node (ref "C62") (pin "2") (pinfunction "2_2") (pintype "passive"))
      (node (ref "C63") (pin "2") (pinfunction "2_2") (pintype "passive"))
      (node (ref "C635") (pin "1") (pinfunction "1_1") (pintype "passive"))
      (node (ref "C636") (pin "1") (pinfunction "1_1") (pintype "passive"))
      (node (ref "C64") (pin "2") (pinfunction "2_2") (pintype "passive"))
      (node (ref "C65") (pin "2") (pinfunction "2_2") (pintype "passive"))
      (node (ref "C66") (pin "2") (pinfunction "2_2") (pintype "passive"))
      (node (ref "C67") (pin "2") (pinfunction "2_2") (pintype "passive"))
      (node (ref "C68") (pin "2") (pinfunction "2_2") (pintype "passive"))
      (node (ref "C69") (pin "2") (pinfunction "2_2") (pintype "passive"))
      (node (ref "C70") (pin "2") (pinfunction "2_2") (pintype "passive"))
      (node (ref "C71") (pin "2") (pinfunction "2_2") (pintype "passive"))
      (node (ref "C72") (pin "2") (pinfunction "2_2") (pintype "passive"))
      (node (ref "C73") (pin "2") (pinfunction "2_2") (pintype "passive"))
      (node (ref "C74") (pin "2") (pinfunction "2_2") (pintype "passive"))
      (node (ref "C75") (pin "2") (pinfunction "2_2") (pintype "passive"))
      (node (ref "C76") (pin "2") (pinfunction "2_2") (pintype "passive"))
      (node (ref "C77") (pin "2") (pinfunction "2_2") (pintype "passive"))
      (node (ref "C78") (pin "2") (pinfunction "2_2") (pintype "passive"))
      (node (ref "C79") (pin "2") (pinfunction "2_2") (pintype "passive"))
      (node (ref "C80") (pin "2") (pinfunction "2_2") (pintype "passive"))
      (node (ref "C81") (pin "1") (pinfunction "1_1") (pintype "passive"))
      (node (ref "C82") (pin "2") (pinfunction "2_2") (pintype "passive"))
      (node (ref "C83") (pin "2") (pinfunction "2_2") (pintype "passive"))
      (node (ref "C84") (pin "1") (pinfunction "1_1") (pintype "passive"))
      (node (ref "C85") (pin "2") (pinfunction "2_2") (pintype "passive"))
      (node (ref "C86") (pin "2") (pinfunction "2_2") (pintype "passive"))
      (node (ref "C87") (pin "2") (pinfunction "2_2") (pintype "passive"))
      (node (ref "C88") (pin "2") (pinfunction "2_2") (pintype "passive"))
      (node (ref "C89") (pin "2") (pinfunction "2_2") (pintype "passive"))
      (node (ref "C90") (pin "2") (pinfunction "2_2") (pintype "passive"))
      (node (ref "C96") (pin "2") (pinfunction "2_2") (pintype "passive"))
      (node (ref "C97") (pin "2") (pinfunction "2_2") (pintype "passive"))
      (node (ref "C98") (pin "2") (pinfunction "2_2") (pintype "passive"))
      (node (ref "C99") (pin "2") (pinfunction "2_2") (pintype "passive"))
      (node (ref "IC22") (pin "A9") (pinfunction "VSS_A9") (pintype "power_in"))
      (node (ref "IC22") (pin "B1") (pinfunction "VSSQ_B1") (pintype "power_in"))
      (node (ref "IC22") (pin "B3") (pinfunction "VSS_B3") (pintype "power_in"))
      (node (ref "IC22") (pin "B9") (pinfunction "VSSQ_B9") (pintype "power_in"))
      (node (ref "IC22") (pin "D1") (pinfunction "VSSQ_D1") (pintype "power_in"))
      (node (ref "IC22") (pin "D8") (pinfunction "VSSQ_D8") (pintype "power_in"))
      (node (ref "IC22") (pin "E1") (pinfunction "VSS_E1") (pintype "power_in"))
      (node (ref "IC22") (pin "E2") (pinfunction "VSSQ_E2") (pintype "power_in"))
      (node (ref "IC22") (pin "E8") (pinfunction "VSSQ_E8") (pintype "power_in"))
      (node (ref "IC22") (pin "F9") (pinfunction "VSSQ_F9") (pintype "power_in"))
      (node (ref "IC22") (pin "G1") (pinfunction "VSSQ_G1") (pintype "power_in"))
      (node (ref "IC22") (pin "G8") (pinfunction "VSS_G8") (pintype "power_in"))
      (node (ref "IC22") (pin "G9") (pinfunction "VSSQ_G9") (pintype "power_in"))
      (node (ref "IC22") (pin "J2") (pinfunction "VSS_J2") (pintype "power_in"))
      (node (ref "IC22") (pin "J8") (pinfunction "VSS_J8") (pintype "power_in"))
      (node (ref "IC22") (pin "M1") (pinfunction "VSS_M1") (pintype "power_in"))
      (node (ref "IC22") (pin "M9") (pinfunction "VSS_M9") (pintype "power_in"))
      (node (ref "IC22") (pin "P1") (pinfunction "VSS_P1") (pintype "power_in"))
      (node (ref "IC22") (pin "P9") (pinfunction "VSS_P9") (pintype "power_in"))
      (node (ref "IC22") (pin "T1") (pinfunction "VSS_T1") (pintype "power_in"))
      (node (ref "IC22") (pin "T9") (pinfunction "VSS_T9") (pintype "power_in"))
      (node (ref "IC23") (pin "A9") (pinfunction "VSS_A9") (pintype "power_in"))
      (node (ref "IC23") (pin "B1") (pinfunction "VSSQ_B1") (pintype "power_in"))
      (node (ref "IC23") (pin "B3") (pinfunction "VSS_B3") (pintype "power_in"))
      (node (ref "IC23") (pin "B9") (pinfunction "VSSQ_B9") (pintype "power_in"))
      (node (ref "IC23") (pin "D1") (pinfunction "VSSQ_D1") (pintype "power_in"))
      (node (ref "IC23") (pin "D8") (pinfunction "VSSQ_D8") (pintype "power_in"))
      (node (ref "IC23") (pin "E1") (pinfunction "VSS_E1") (pintype "power_in"))
      (node (ref "IC23") (pin "E2") (pinfunction "VSSQ_E2") (pintype "power_in"))
      (node (ref "IC23") (pin "E8") (pinfunction "VSSQ_E8") (pintype "power_in"))
      (node (ref "IC23") (pin "F9") (pinfunction "VSSQ_F9") (pintype "power_in"))
      (node (ref "IC23") (pin "G1") (pinfunction "VSSQ_G1") (pintype "power_in"))
      (node (ref "IC23") (pin "G8") (pinfunction "VSS_G8") (pintype "power_in"))
      (node (ref "IC23") (pin "G9") (pinfunction "VSSQ_G9") (pintype "power_in"))
      (node (ref "IC23") (pin "J2") (pinfunction "VSS_J2") (pintype "power_in"))
      (node (ref "IC23") (pin "J8") (pinfunction "VSS_J8") (pintype "power_in"))
      (node (ref "IC23") (pin "M1") (pinfunction "VSS_M1") (pintype "power_in"))
      (node (ref "IC23") (pin "M9") (pinfunction "VSS_M9") (pintype "power_in"))
      (node (ref "IC23") (pin "P1") (pinfunction "VSS_P1") (pintype "power_in"))
      (node (ref "IC23") (pin "P9") (pinfunction "VSS_P9") (pintype "power_in"))
      (node (ref "IC23") (pin "T1") (pinfunction "VSS_T1") (pintype "power_in"))
      (node (ref "IC23") (pin "T9") (pinfunction "VSS_T9") (pintype "power_in"))
      (node (ref "IC25") (pin "A9") (pinfunction "VSS_A9") (pintype "power_in"))
      (node (ref "IC25") (pin "B1") (pinfunction "VSSQ_B1") (pintype "power_in"))
      (node (ref "IC25") (pin "B3") (pinfunction "VSS_B3") (pintype "power_in"))
      (node (ref "IC25") (pin "B9") (pinfunction "VSSQ_B9") (pintype "power_in"))
      (node (ref "IC25") (pin "D1") (pinfunction "VSSQ_D1") (pintype "power_in"))
      (node (ref "IC25") (pin "D8") (pinfunction "VSSQ_D8") (pintype "power_in"))
      (node (ref "IC25") (pin "E1") (pinfunction "VSS_E1") (pintype "power_in"))
      (node (ref "IC25") (pin "E2") (pinfunction "VSSQ_E2") (pintype "power_in"))
      (node (ref "IC25") (pin "E8") (pinfunction "VSSQ_E8") (pintype "power_in"))
      (node (ref "IC25") (pin "F9") (pinfunction "VSSQ_F9") (pintype "power_in"))
      (node (ref "IC25") (pin "G1") (pinfunction "VSSQ_G1") (pintype "power_in"))
      (node (ref "IC25") (pin "G8") (pinfunction "VSS_G8") (pintype "power_in"))
      (node (ref "IC25") (pin "G9") (pinfunction "VSSQ_G9") (pintype "power_in"))
      (node (ref "IC25") (pin "J2") (pinfunction "VSS_J2") (pintype "power_in"))
      (node (ref "IC25") (pin "J8") (pinfunction "VSS_J8") (pintype "power_in"))
      (node (ref "IC25") (pin "M1") (pinfunction "VSS_M1") (pintype "power_in"))
      (node (ref "IC25") (pin "M9") (pinfunction "VSS_M9") (pintype "power_in"))
      (node (ref "IC25") (pin "P1") (pinfunction "VSS_P1") (pintype "power_in"))
      (node (ref "IC25") (pin "P9") (pinfunction "VSS_P9") (pintype "power_in"))
      (node (ref "IC25") (pin "T1") (pinfunction "VSS_T1") (pintype "power_in"))
      (node (ref "IC25") (pin "T9") (pinfunction "VSS_T9") (pintype "power_in"))
      (node (ref "IC28") (pin "11") (pinfunction "EP_11") (pintype "power_in"))
      (node (ref "IC28") (pin "4") (pinfunction "PGND_4") (pintype "power_in"))
      (node (ref "IC28") (pin "8") (pinfunction "GND_8") (pintype "power_in"))
      (node (ref "IC4") (pin "A9") (pinfunction "VSS_A9") (pintype "power_in"))
      (node (ref "IC4") (pin "B1") (pinfunction "VSSQ_B1") (pintype "power_in"))
      (node (ref "IC4") (pin "B3") (pinfunction "VSS_B3") (pintype "power_in"))
      (node (ref "IC4") (pin "B9") (pinfunction "VSSQ_B9") (pintype "power_in"))
      (node (ref "IC4") (pin "D1") (pinfunction "VSSQ_D1") (pintype "power_in"))
      (node (ref "IC4") (pin "D8") (pinfunction "VSSQ_D8") (pintype "power_in"))
      (node (ref "IC4") (pin "E1") (pinfunction "VSS_E1") (pintype "power_in"))
      (node (ref "IC4") (pin "E2") (pinfunction "VSSQ_E2") (pintype "power_in"))
      (node (ref "IC4") (pin "E8") (pinfunction "VSSQ_E8") (pintype "power_in"))
      (node (ref "IC4") (pin "F9") (pinfunction "VSSQ_F9") (pintype "power_in"))
      (node (ref "IC4") (pin "G1") (pinfunction "VSSQ_G1") (pintype "power_in"))
      (node (ref "IC4") (pin "G8") (pinfunction "VSS_G8") (pintype "power_in"))
      (node (ref "IC4") (pin "G9") (pinfunction "VSSQ_G9") (pintype "power_in"))
      (node (ref "IC4") (pin "J2") (pinfunction "VSS_J2") (pintype "power_in"))
      (node (ref "IC4") (pin "J8") (pinfunction "VSS_J8") (pintype "power_in"))
      (node (ref "IC4") (pin "M1") (pinfunction "VSS_M1") (pintype "power_in"))
      (node (ref "IC4") (pin "M9") (pinfunction "VSS_M9") (pintype "power_in"))
      (node (ref "IC4") (pin "P1") (pinfunction "VSS_P1") (pintype "power_in"))
      (node (ref "IC4") (pin "P9") (pinfunction "VSS_P9") (pintype "power_in"))
      (node (ref "IC4") (pin "T1") (pinfunction "VSS_T1") (pintype "power_in"))
      (node (ref "IC4") (pin "T9") (pinfunction "VSS_T9") (pintype "power_in"))
      (node (ref "R106") (pin "1") (pinfunction "1_1") (pintype "passive"))
      (node (ref "R108") (pin "1") (pinfunction "1_1") (pintype "passive"))
      (node (ref "R109") (pin "1") (pinfunction "1_1") (pintype "passive"))
      (node (ref "R135") (pin "1") (pinfunction "1_1") (pintype "passive"))
      (node (ref "R136") (pin "1") (pinfunction "1_1") (pintype "passive"))
      (node (ref "R137") (pin "1") (pinfunction "1_1") (pintype "passive"))
    )
    (net (code "128") (name "Net-(IC4-ZQ)") (class "Default")
      (node (ref "IC4") (pin "L8") (pinfunction "ZQ_L8") (pintype "input"))
      (node (ref "R136") (pin "2") (pinfunction "2_2") (pintype "passive"))
    )
    (net (code "129") (name "Net-(IC23-ZQ)") (class "Default")
      (node (ref "IC23") (pin "L8") (pinfunction "ZQ_L8") (pintype "input"))
      (node (ref "R108") (pin "2") (pinfunction "2_2") (pintype "passive"))
    )
    (net (code "130") (name "Net-(IC25-ZQ)") (class "Default")
      (node (ref "IC25") (pin "L8") (pinfunction "ZQ_L8") (pintype "input"))
      (node (ref "R137") (pin "2") (pinfunction "2_2") (pintype "passive"))
    )
    (net (code "131") (name "P1V5") (class "Default")
      (node (ref "C100") (pin "1") (pinfunction "1_1") (pintype "passive"))
      (node (ref "C101") (pin "1") (pinfunction "1_1") (pintype "passive"))
      (node (ref "C102") (pin "1") (pinfunction "1_1") (pintype "passive"))
      (node (ref "C103") (pin "1") (pinfunction "1_1") (pintype "passive"))
      (node (ref "C104") (pin "1") (pinfunction "1_1") (pintype "passive"))
      (node (ref "C105") (pin "1") (pinfunction "1_1") (pintype "passive"))
      (node (ref "C106") (pin "1") (pinfunction "1_1") (pintype "passive"))
      (node (ref "C107") (pin "1") (pinfunction "1_1") (pintype "passive"))
      (node (ref "C108") (pin "1") (pinfunction "1_1") (pintype "passive"))
      (node (ref "C109") (pin "1") (pinfunction "1_1") (pintype "passive"))
      (node (ref "C110") (pin "1") (pinfunction "1_1") (pintype "passive"))
      (node (ref "C111") (pin "1") (pinfunction "1_1") (pintype "passive"))
      (node (ref "C112") (pin "2") (pinfunction "2_2") (pintype "passive"))
      (node (ref "C275") (pin "1") (pinfunction "1_1") (pintype "passive"))
      (node (ref "C278") (pin "1") (pinfunction "1_1") (pintype "passive"))
      (node (ref "C343") (pin "1") (pinfunction "1_1") (pintype "passive"))
      (node (ref "C354") (pin "1") (pinfunction "1_1") (pintype "passive"))
      (node (ref "C355") (pin "1") (pinfunction "1_1") (pintype "passive"))
      (node (ref "C427") (pin "1") (pinfunction "1_1") (pintype "passive"))
      (node (ref "C428") (pin "1") (pinfunction "1_1") (pintype "passive"))
      (node (ref "C429") (pin "1") (pinfunction "1_1") (pintype "passive"))
      (node (ref "C430") (pin "1") (pinfunction "1_1") (pintype "passive"))
      (node (ref "C432") (pin "1") (pinfunction "1_1") (pintype "passive"))
      (node (ref "C433") (pin "1") (pinfunction "1_1") (pintype "passive"))
      (node (ref "C434") (pin "1") (pinfunction "1_1") (pintype "passive"))
      (node (ref "C435") (pin "1") (pinfunction "1_1") (pintype "passive"))
      (node (ref "C436") (pin "1") (pinfunction "1_1") (pintype "passive"))
      (node (ref "C56") (pin "1") (pinfunction "1_1") (pintype "passive"))
      (node (ref "C57") (pin "1") (pinfunction "1_1") (pintype "passive"))
      (node (ref "C58") (pin "1") (pinfunction "1_1") (pintype "passive"))
      (node (ref "C59") (pin "1") (pinfunction "1_1") (pintype "passive"))
      (node (ref "C60") (pin "1") (pinfunction "1_1") (pintype "passive"))
      (node (ref "C61") (pin "1") (pinfunction "1_1") (pintype "passive"))
      (node (ref "C62") (pin "1") (pinfunction "1_1") (pintype "passive"))
      (node (ref "C63") (pin "1") (pinfunction "1_1") (pintype "passive"))
      (node (ref "C64") (pin "1") (pinfunction "1_1") (pintype "passive"))
      (node (ref "C65") (pin "1") (pinfunction "1_1") (pintype "passive"))
      (node (ref "C66") (pin "1") (pinfunction "1_1") (pintype "passive"))
      (node (ref "C67") (pin "1") (pinfunction "1_1") (pintype "passive"))
      (node (ref "C68") (pin "1") (pinfunction "1_1") (pintype "passive"))
      (node (ref "C69") (pin "1") (pinfunction "1_1") (pintype "passive"))
      (node (ref "C70") (pin "1") (pinfunction "1_1") (pintype "passive"))
      (node (ref "C71") (pin "1") (pinfunction "1_1") (pintype "passive"))
      (node (ref "C72") (pin "1") (pinfunction "1_1") (pintype "passive"))
      (node (ref "C73") (pin "1") (pinfunction "1_1") (pintype "passive"))
      (node (ref "C74") (pin "1") (pinfunction "1_1") (pintype "passive"))
      (node (ref "C75") (pin "1") (pinfunction "1_1") (pintype "passive"))
      (node (ref "C76") (pin "1") (pinfunction "1_1") (pintype "passive"))
      (node (ref "C77") (pin "1") (pinfunction "1_1") (pintype "passive"))
      (node (ref "C78") (pin "1") (pinfunction "1_1") (pintype "passive"))
      (node (ref "C81") (pin "2") (pinfunction "2_2") (pintype "passive"))
      (node (ref "C89") (pin "1") (pinfunction "1_1") (pintype "passive"))
      (node (ref "C90") (pin "1") (pinfunction "1_1") (pintype "passive"))
      (node (ref "C96") (pin "1") (pinfunction "1_1") (pintype "passive"))
      (node (ref "C97") (pin "1") (pinfunction "1_1") (pintype "passive"))
      (node (ref "C98") (pin "1") (pinfunction "1_1") (pintype "passive"))
      (node (ref "C99") (pin "1") (pinfunction "1_1") (pintype "passive"))
      (node (ref "IC22") (pin "A1") (pinfunction "VDDQ_A1") (pintype "power_in"))
      (node (ref "IC22") (pin "A8") (pinfunction "VDDQ_A8") (pintype "power_in"))
      (node (ref "IC22") (pin "B2") (pinfunction "VDD_B2") (pintype "power_in"))
      (node (ref "IC22") (pin "C1") (pinfunction "VDDQ_C1") (pintype "power_in"))
      (node (ref "IC22") (pin "C9") (pinfunction "VDDQ_C9") (pintype "power_in"))
      (node (ref "IC22") (pin "D2") (pinfunction "VDDQ_D2") (pintype "power_in"))
      (node (ref "IC22") (pin "D9") (pinfunction "VDD_D9") (pintype "power_in"))
      (node (ref "IC22") (pin "E9") (pinfunction "VDDQ_E9") (pintype "power_in"))
      (node (ref "IC22") (pin "F1") (pinfunction "VDDQ_F1") (pintype "power_in"))
      (node (ref "IC22") (pin "G7") (pinfunction "VDD_G7") (pintype "power_in"))
      (node (ref "IC22") (pin "H2") (pinfunction "VDDQ_H2") (pintype "power_in"))
      (node (ref "IC22") (pin "H9") (pinfunction "VDDQ_H9") (pintype "power_in"))
      (node (ref "IC22") (pin "K2") (pinfunction "VDD_K2") (pintype "power_in"))
      (node (ref "IC22") (pin "K8") (pinfunction "VDD_K8") (pintype "power_in"))
      (node (ref "IC22") (pin "N1") (pinfunction "VDD_N1") (pintype "power_in"))
      (node (ref "IC22") (pin "N9") (pinfunction "VDD_N9") (pintype "power_in"))
      (node (ref "IC22") (pin "R1") (pinfunction "VDD_R1") (pintype "power_in"))
      (node (ref "IC22") (pin "R9") (pinfunction "VDD_R9") (pintype "power_in"))
      (node (ref "IC23") (pin "A1") (pinfunction "VDDQ_A1") (pintype "power_in"))
      (node (ref "IC23") (pin "A8") (pinfunction "VDDQ_A8") (pintype "power_in"))
      (node (ref "IC23") (pin "B2") (pinfunction "VDD_B2") (pintype "power_in"))
      (node (ref "IC23") (pin "C1") (pinfunction "VDDQ_C1") (pintype "power_in"))
      (node (ref "IC23") (pin "C9") (pinfunction "VDDQ_C9") (pintype "power_in"))
      (node (ref "IC23") (pin "D2") (pinfunction "VDDQ_D2") (pintype "power_in"))
      (node (ref "IC23") (pin "D9") (pinfunction "VDD_D9") (pintype "power_in"))
      (node (ref "IC23") (pin "E9") (pinfunction "VDDQ_E9") (pintype "power_in"))
      (node (ref "IC23") (pin "F1") (pinfunction "VDDQ_F1") (pintype "power_in"))
      (node (ref "IC23") (pin "G7") (pinfunction "VDD_G7") (pintype "power_in"))
      (node (ref "IC23") (pin "H2") (pinfunction "VDDQ_H2") (pintype "power_in"))
      (node (ref "IC23") (pin "H9") (pinfunction "VDDQ_H9") (pintype "power_in"))
      (node (ref "IC23") (pin "K2") (pinfunction "VDD_K2") (pintype "power_in"))
      (node (ref "IC23") (pin "K8") (pinfunction "VDD_K8") (pintype "power_in"))
      (node (ref "IC23") (pin "N1") (pinfunction "VDD_N1") (pintype "power_in"))
      (node (ref "IC23") (pin "N9") (pinfunction "VDD_N9") (pintype "power_in"))
      (node (ref "IC23") (pin "R1") (pinfunction "VDD_R1") (pintype "power_in"))
      (node (ref "IC23") (pin "R9") (pinfunction "VDD_R9") (pintype "power_in"))
      (node (ref "IC25") (pin "A1") (pinfunction "VDDQ_A1") (pintype "power_in"))
      (node (ref "IC25") (pin "A8") (pinfunction "VDDQ_A8") (pintype "power_in"))
      (node (ref "IC25") (pin "B2") (pinfunction "VDD_B2") (pintype "power_in"))
      (node (ref "IC25") (pin "C1") (pinfunction "VDDQ_C1") (pintype "power_in"))
      (node (ref "IC25") (pin "C9") (pinfunction "VDDQ_C9") (pintype "power_in"))
      (node (ref "IC25") (pin "D2") (pinfunction "VDDQ_D2") (pintype "power_in"))
      (node (ref "IC25") (pin "D9") (pinfunction "VDD_D9") (pintype "power_in"))
      (node (ref "IC25") (pin "E9") (pinfunction "VDDQ_E9") (pintype "power_in"))
      (node (ref "IC25") (pin "F1") (pinfunction "VDDQ_F1") (pintype "power_in"))
      (node (ref "IC25") (pin "G7") (pinfunction "VDD_G7") (pintype "power_in"))
      (node (ref "IC25") (pin "H2") (pinfunction "VDDQ_H2") (pintype "power_in"))
      (node (ref "IC25") (pin "H9") (pinfunction "VDDQ_H9") (pintype "power_in"))
      (node (ref "IC25") (pin "K2") (pinfunction "VDD_K2") (pintype "power_in"))
      (node (ref "IC25") (pin "K8") (pinfunction "VDD_K8") (pintype "power_in"))
      (node (ref "IC25") (pin "N1") (pinfunction "VDD_N1") (pintype "power_in"))
      (node (ref "IC25") (pin "N9") (pinfunction "VDD_N9") (pintype "power_in"))
      (node (ref "IC25") (pin "R1") (pinfunction "VDD_R1") (pintype "power_in"))
      (node (ref "IC25") (pin "R9") (pinfunction "VDD_R9") (pintype "power_in"))
      (node (ref "IC28") (pin "2") (pinfunction "VLDOIN_2") (pintype "input"))
      (node (ref "IC4") (pin "A1") (pinfunction "VDDQ_A1") (pintype "power_in"))
      (node (ref "IC4") (pin "A8") (pinfunction "VDDQ_A8") (pintype "power_in"))
      (node (ref "IC4") (pin "B2") (pinfunction "VDD_B2") (pintype "power_in"))
      (node (ref "IC4") (pin "C1") (pinfunction "VDDQ_C1") (pintype "power_in"))
      (node (ref "IC4") (pin "C9") (pinfunction "VDDQ_C9") (pintype "power_in"))
      (node (ref "IC4") (pin "D2") (pinfunction "VDDQ_D2") (pintype "power_in"))
      (node (ref "IC4") (pin "D9") (pinfunction "VDD_D9") (pintype "power_in"))
      (node (ref "IC4") (pin "E9") (pinfunction "VDDQ_E9") (pintype "power_in"))
      (node (ref "IC4") (pin "F1") (pinfunction "VDDQ_F1") (pintype "power_in"))
      (node (ref "IC4") (pin "G7") (pinfunction "VDD_G7") (pintype "power_in"))
      (node (ref "IC4") (pin "H2") (pinfunction "VDDQ_H2") (pintype "power_in"))
      (node (ref "IC4") (pin "H9") (pinfunction "VDDQ_H9") (pintype "power_in"))
      (node (ref "IC4") (pin "K2") (pinfunction "VDD_K2") (pintype "power_in"))
      (node (ref "IC4") (pin "K8") (pinfunction "VDD_K8") (pintype "power_in"))
      (node (ref "IC4") (pin "N1") (pinfunction "VDD_N1") (pintype "power_in"))
      (node (ref "IC4") (pin "N9") (pinfunction "VDD_N9") (pintype "power_in"))
      (node (ref "IC4") (pin "R1") (pinfunction "VDD_R1") (pintype "power_in"))
      (node (ref "IC4") (pin "R9") (pinfunction "VDD_R9") (pintype "power_in"))
      (node (ref "R340") (pin "1") (pinfunction "1_1") (pintype "passive"))
    )
    (net (code "132") (name "P3V3") (class "Default")
      (node (ref "C431") (pin "1") (pinfunction "1_1") (pintype "passive"))
      (node (ref "IC28") (pin "10") (pinfunction "VIN_10") (pintype "input"))
      (node (ref "IC28") (pin "7") (pinfunction "EN_7") (pintype "input"))
    )
    (net (code "133") (name "VTT64") (class "Default")
      (node (ref "C426") (pin "1") (pinfunction "1_1") (pintype "passive"))
      (node (ref "C44") (pin "1") (pinfunction "1_1") (pintype "passive"))
      (node (ref "C45") (pin "1") (pinfunction "1_1") (pintype "passive"))
      (node (ref "C46") (pin "1") (pinfunction "1_1") (pintype "passive"))
      (node (ref "C47") (pin "1") (pinfunction "1_1") (pintype "passive"))
      (node (ref "C48") (pin "1") (pinfunction "1_1") (pintype "passive"))
      (node (ref "C49") (pin "1") (pinfunction "1_1") (pintype "passive"))
      (node (ref "C50") (pin "1") (pinfunction "1_1") (pintype "passive"))
      (node (ref "C51") (pin "1") (pinfunction "1_1") (pintype "passive"))
      (node (ref "C52") (pin "1") (pinfunction "1_1") (pintype "passive"))
      (node (ref "C53") (pin "1") (pinfunction "1_1") (pintype "passive"))
      (node (ref "C54") (pin "1") (pinfunction "1_1") (pintype "passive"))
      (node (ref "C55") (pin "1") (pinfunction "1_1") (pintype "passive"))
      (node (ref "C635") (pin "2") (pinfunction "2_2") (pintype "passive"))
      (node (ref "C636") (pin "2") (pinfunction "2_2") (pintype "passive"))
      (node (ref "IC28") (pin "3") (pinfunction "VO_3") (pintype "power_in"))
      (node (ref "R107") (pin "2") (pinfunction "2_2") (pintype "passive"))
      (node (ref "R110") (pin "1") (pinfunction "1_1") (pintype "passive"))
      (node (ref "R111") (pin "1") (pinfunction "1_1") (pintype "passive"))
      (node (ref "R112") (pin "1") (pinfunction "1_1") (pintype "passive"))
      (node (ref "R113") (pin "1") (pinfunction "1_1") (pintype "passive"))
      (node (ref "R114") (pin "1") (pinfunction "1_1") (pintype "passive"))
      (node (ref "R115") (pin "1") (pinfunction "1_1") (pintype "passive"))
      (node (ref "R116") (pin "1") (pinfunction "1_1") (pintype "passive"))
      (node (ref "R117") (pin "1") (pinfunction "1_1") (pintype "passive"))
      (node (ref "R118") (pin "1") (pinfunction "1_1") (pintype "passive"))
      (node (ref "R119") (pin "1") (pinfunction "1_1") (pintype "passive"))
      (node (ref "R120") (pin "1") (pinfunction "1_1") (pintype "passive"))
      (node (ref "R121") (pin "1") (pinfunction "1_1") (pintype "passive"))
      (node (ref "R122") (pin "1") (pinfunction "1_1") (pintype "passive"))
      (node (ref "R123") (pin "1") (pinfunction "1_1") (pintype "passive"))
      (node (ref "R124") (pin "1") (pinfunction "1_1") (pintype "passive"))
      (node (ref "R125") (pin "1") (pinfunction "1_1") (pintype "passive"))
      (node (ref "R126") (pin "1") (pinfunction "1_1") (pintype "passive"))
      (node (ref "R127") (pin "1") (pinfunction "1_1") (pintype "passive"))
      (node (ref "R128") (pin "1") (pinfunction "1_1") (pintype "passive"))
      (node (ref "R129") (pin "1") (pinfunction "1_1") (pintype "passive"))
      (node (ref "R130") (pin "1") (pinfunction "1_1") (pintype "passive"))
      (node (ref "R131") (pin "1") (pinfunction "1_1") (pintype "passive"))
      (node (ref "R132") (pin "1") (pinfunction "1_1") (pintype "passive"))
      (node (ref "R133") (pin "1") (pinfunction "1_1") (pintype "passive"))
      (node (ref "R134") (pin "1") (pinfunction "1_1") (pintype "passive"))
      (node (ref "R138") (pin "1") (pinfunction "1_1") (pintype "passive"))
    )
    (net (code "134") (name "unconnected-(IC4-NC-PadJ1)") (class "Default")
      (node (ref "IC4") (pin "J1") (pinfunction "NC_J1") (pintype "passive"))
    )
    (net (code "135") (name "unconnected-(IC4-NC-PadJ9)") (class "Default")
      (node (ref "IC4") (pin "J9") (pinfunction "NC_J9") (pintype "passive"))
    )
    (net (code "136") (name "unconnected-(IC4-NC-PadL1)") (class "Default")
      (node (ref "IC4") (pin "L1") (pinfunction "NC_L1") (pintype "passive"))
    )
    (net (code "137") (name "unconnected-(IC4-NC-PadL9)") (class "Default")
      (node (ref "IC4") (pin "L9") (pinfunction "NC_L9") (pintype "passive"))
    )
    (net (code "138") (name "unconnected-(IC4-NC-PadM7)") (class "Default")
      (node (ref "IC4") (pin "M7") (pinfunction "NC_M7") (pintype "passive"))
    )
    (net (code "139") (name "unconnected-(IC22-NC-PadJ1)") (class "Default")
      (node (ref "IC22") (pin "J1") (pinfunction "NC_J1") (pintype "passive"))
    )
    (net (code "140") (name "unconnected-(IC22-NC-PadJ9)") (class "Default")
      (node (ref "IC22") (pin "J9") (pinfunction "NC_J9") (pintype "passive"))
    )
    (net (code "141") (name "unconnected-(IC22-NC-PadL1)") (class "Default")
      (node (ref "IC22") (pin "L1") (pinfunction "NC_L1") (pintype "passive"))
    )
    (net (code "142") (name "unconnected-(IC22-NC-PadL9)") (class "Default")
      (node (ref "IC22") (pin "L9") (pinfunction "NC_L9") (pintype "passive"))
    )
    (net (code "143") (name "unconnected-(IC22-NC-PadM7)") (class "Default")
      (node (ref "IC22") (pin "M7") (pinfunction "NC_M7") (pintype "passive"))
    )
    (net (code "144") (name "unconnected-(IC23-NC-PadJ1)") (class "Default")
      (node (ref "IC23") (pin "J1") (pinfunction "NC_J1") (pintype "passive"))
    )
    (net (code "145") (name "unconnected-(IC23-NC-PadJ9)") (class "Default")
      (node (ref "IC23") (pin "J9") (pinfunction "NC_J9") (pintype "passive"))
    )
    (net (code "146") (name "unconnected-(IC23-NC-PadL1)") (class "Default")
      (node (ref "IC23") (pin "L1") (pinfunction "NC_L1") (pintype "passive"))
    )
    (net (code "147") (name "unconnected-(IC23-NC-PadL9)") (class "Default")
      (node (ref "IC23") (pin "L9") (pinfunction "NC_L9") (pintype "passive"))
    )
    (net (code "148") (name "unconnected-(IC23-NC-PadM7)") (class "Default")
      (node (ref "IC23") (pin "M7") (pinfunction "NC_M7") (pintype "passive"))
    )
    (net (code "149") (name "unconnected-(IC25-NC-PadJ1)") (class "Default")
      (node (ref "IC25") (pin "J1") (pinfunction "NC_J1") (pintype "passive"))
    )
    (net (code "150") (name "unconnected-(IC25-NC-PadJ9)") (class "Default")
      (node (ref "IC25") (pin "J9") (pinfunction "NC_J9") (pintype "passive"))
    )
    (net (code "151") (name "unconnected-(IC25-NC-PadL1)") (class "Default")
      (node (ref "IC25") (pin "L1") (pinfunction "NC_L1") (pintype "passive"))
    )
    (net (code "152") (name "unconnected-(IC25-NC-PadL9)") (class "Default")
      (node (ref "IC25") (pin "L9") (pinfunction "NC_L9") (pintype "passive"))
    )
    (net (code "153") (name "unconnected-(IC25-NC-PadM7)") (class "Default")
      (node (ref "IC25") (pin "M7") (pinfunction "NC_M7") (pintype "passive"))
    )
  )
)
